# GaN_Fet_ESC_V0_1.net
KiCad netlist of a schematic drawn in EAGLE
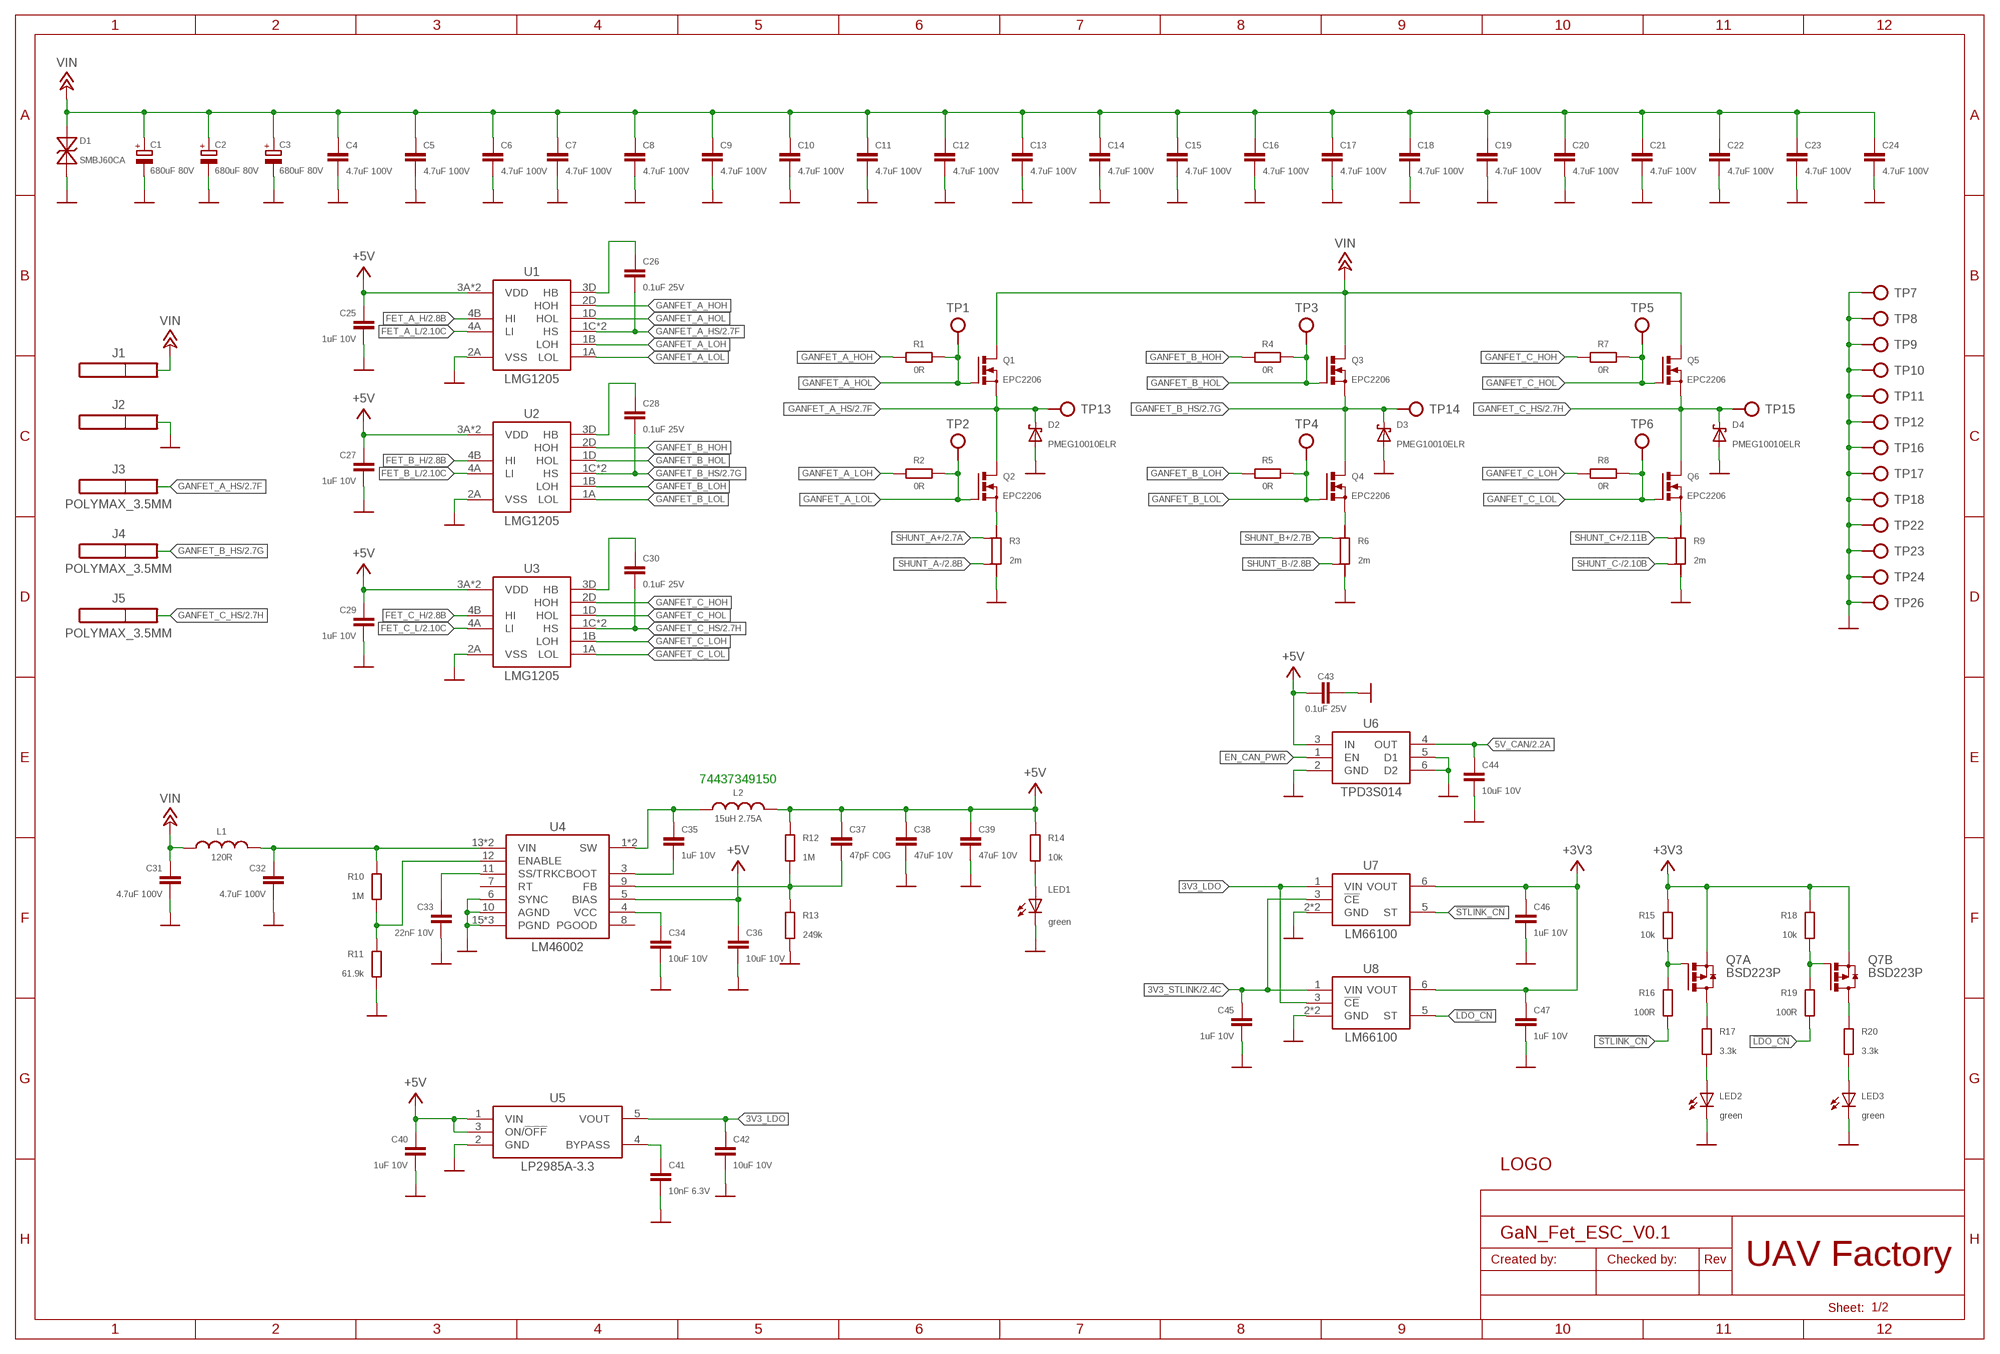
[diagram p0: schematic, sheet 1]
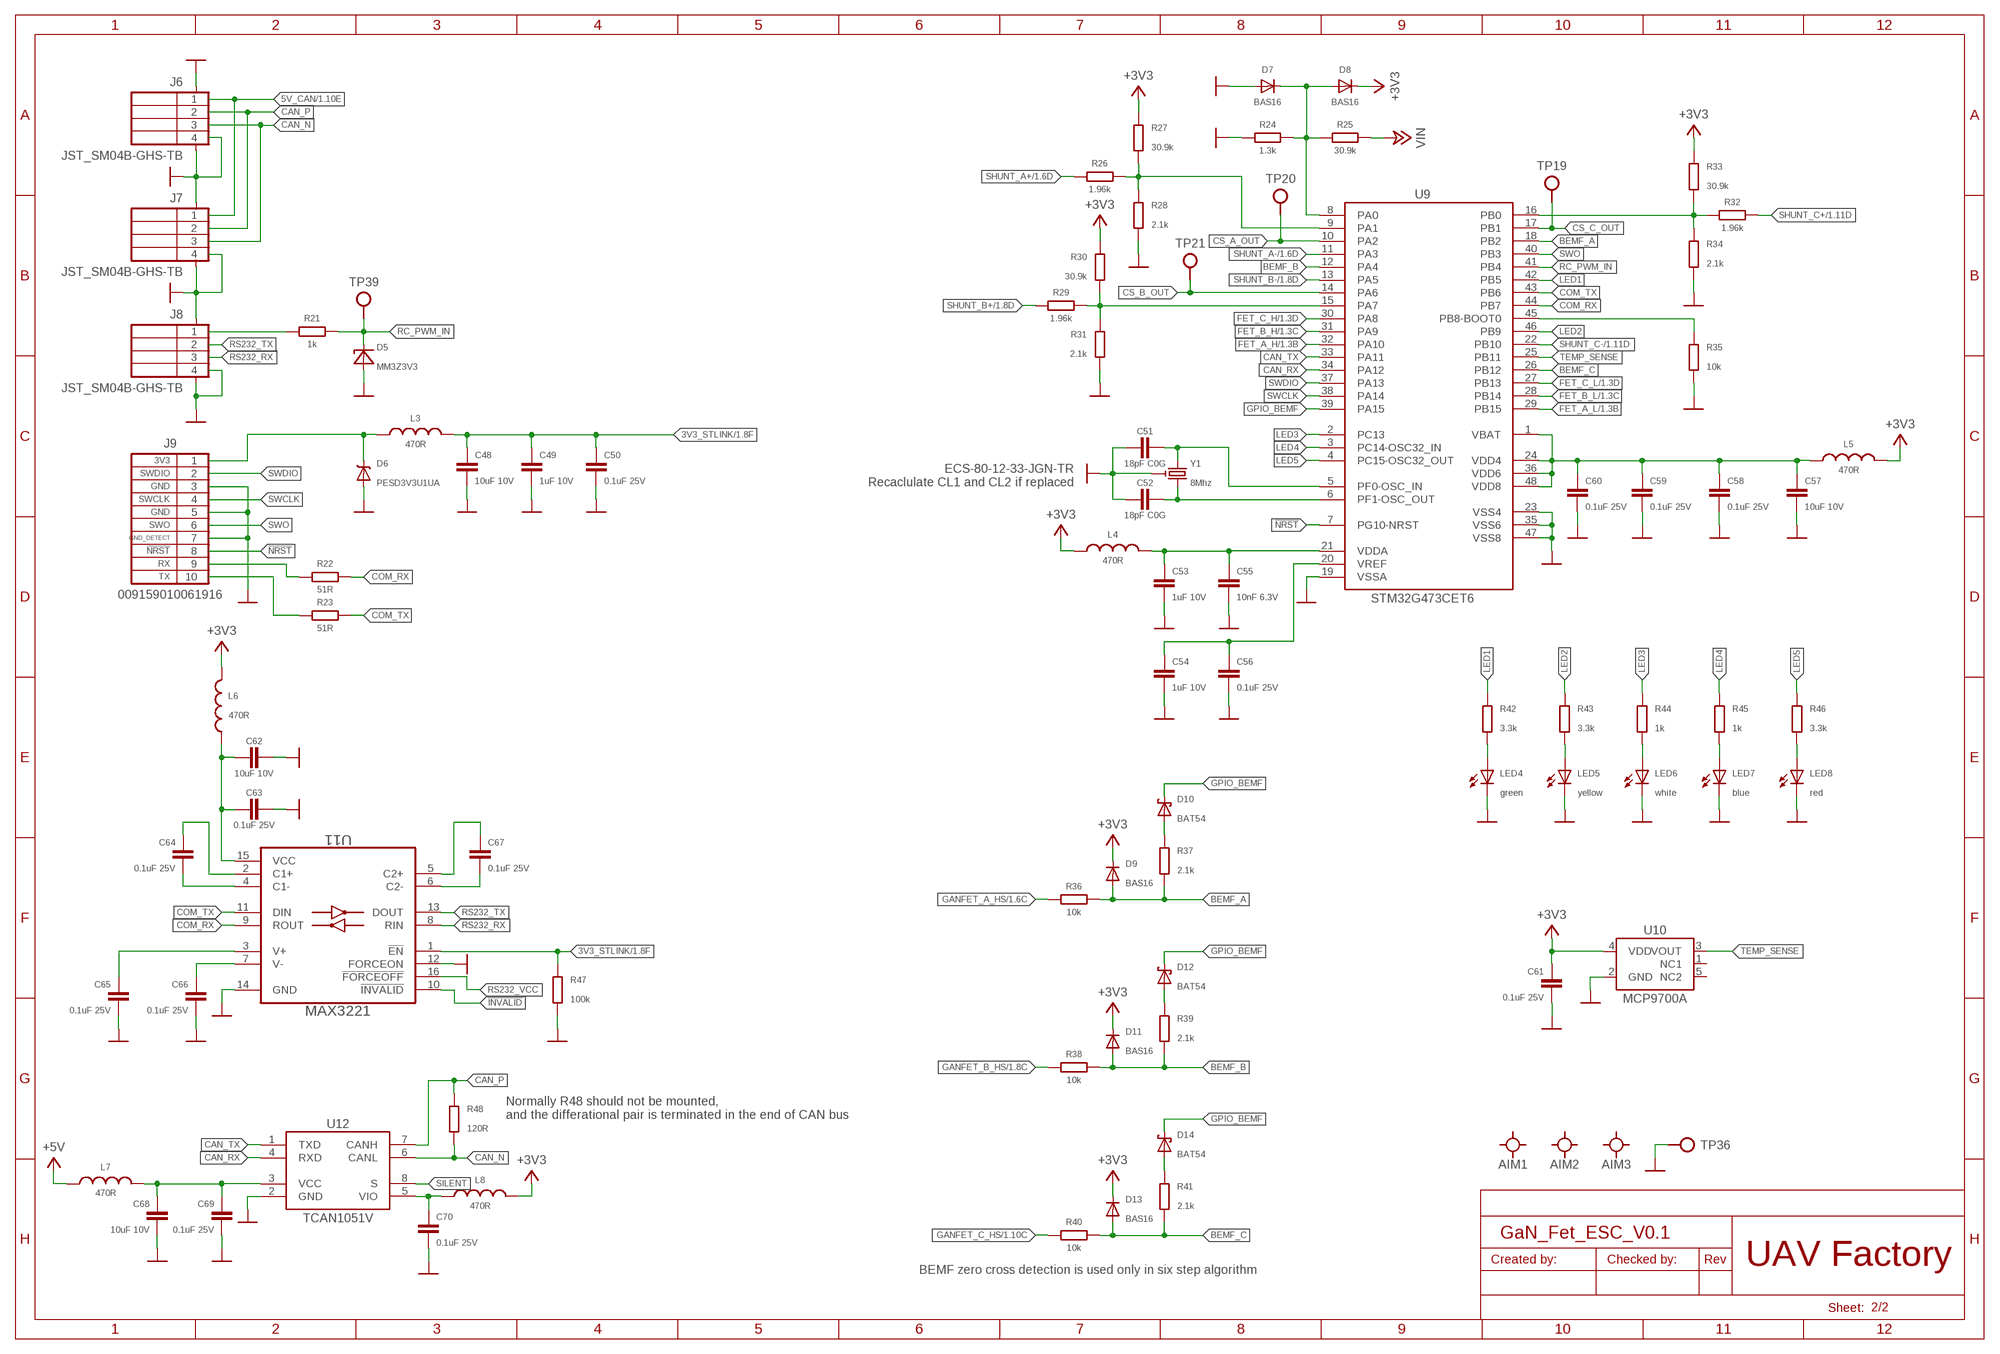
[diagram p1: schematic, sheet 2]

(export (version "E")
  (design (tool "Eeschema 10.0.6"))
  (components
    (comp (ref "AIM1")
      (value "AIM_1_MM")
      (footprint "eagle-import:AIM_1_MM")
      (libsource (lib "eagle-import") (part "AIM_1_MM"))
    )
    (comp (ref "AIM2")
      (value "AIM_1_MM")
      (footprint "eagle-import:AIM_1_MM")
      (libsource (lib "eagle-import") (part "AIM_1_MM"))
    )
    (comp (ref "AIM3")
      (value "AIM_1_MM")
      (footprint "eagle-import:AIM_1_MM")
      (libsource (lib "eagle-import") (part "AIM_1_MM"))
    )
    (comp (ref "C48")
      (value "10uF 10V")
      (footprint "eagle-import:C0603")
      (libsource (lib "eagle-import") (part "CAPACITOR_CERAMIC/0603"))
    )
    (comp (ref "C49")
      (value "1uF 10V")
      (footprint "eagle-import:C0402")
      (libsource (lib "eagle-import") (part "CAPACITOR_CERAMIC/0402"))
    )
    (comp (ref "C50")
      (value "0.1uF 25V")
      (footprint "eagle-import:C0402")
      (libsource (lib "eagle-import") (part "CAPACITOR_CERAMIC/0402"))
    )
    (comp (ref "C51")
      (value "18pF C0G")
      (footprint "eagle-import:C0402")
      (libsource (lib "eagle-import") (part "CAPACITOR_CERAMIC/0402"))
    )
    (comp (ref "C52")
      (value "18pF C0G")
      (footprint "eagle-import:C0402")
      (libsource (lib "eagle-import") (part "CAPACITOR_CERAMIC/0402"))
    )
    (comp (ref "C53")
      (value "1uF 10V")
      (footprint "eagle-import:C0402")
      (libsource (lib "eagle-import") (part "CAPACITOR_CERAMIC/0402"))
    )
    (comp (ref "C54")
      (value "1uF 10V")
      (footprint "eagle-import:C0402")
      (libsource (lib "eagle-import") (part "CAPACITOR_CERAMIC/0402"))
    )
    (comp (ref "C55")
      (value "10nF 6.3V")
      (footprint "eagle-import:C0402")
      (libsource (lib "eagle-import") (part "CAPACITOR_CERAMIC/0402"))
    )
    (comp (ref "C56")
      (value "0.1uF 25V")
      (footprint "eagle-import:C0402")
      (libsource (lib "eagle-import") (part "CAPACITOR_CERAMIC/0402"))
    )
    (comp (ref "C57")
      (value "10uF 10V")
      (footprint "eagle-import:C0603")
      (libsource (lib "eagle-import") (part "CAPACITOR_CERAMIC/0603"))
    )
    (comp (ref "C58")
      (value "0.1uF 25V")
      (footprint "eagle-import:C0402")
      (libsource (lib "eagle-import") (part "CAPACITOR_CERAMIC/0402"))
    )
    (comp (ref "C59")
      (value "0.1uF 25V")
      (footprint "eagle-import:C0402")
      (libsource (lib "eagle-import") (part "CAPACITOR_CERAMIC/0402"))
    )
    (comp (ref "C60")
      (value "0.1uF 25V")
      (footprint "eagle-import:C0402")
      (libsource (lib "eagle-import") (part "CAPACITOR_CERAMIC/0402"))
    )
    (comp (ref "C61")
      (value "0.1uF 25V")
      (footprint "eagle-import:C0402")
      (libsource (lib "eagle-import") (part "CAPACITOR_CERAMIC/0402"))
    )
    (comp (ref "C62")
      (value "10uF 10V")
      (footprint "eagle-import:C0603")
      (libsource (lib "eagle-import") (part "CAPACITOR_CERAMIC/0603"))
    )
    (comp (ref "C63")
      (value "0.1uF 25V")
      (footprint "eagle-import:C0402")
      (libsource (lib "eagle-import") (part "CAPACITOR_CERAMIC/0402"))
    )
    (comp (ref "C64")
      (value "0.1uF 25V")
      (footprint "eagle-import:C0402")
      (libsource (lib "eagle-import") (part "CAPACITOR_CERAMIC/0402"))
    )
    (comp (ref "C65")
      (value "0.1uF 25V")
      (footprint "eagle-import:C0402")
      (libsource (lib "eagle-import") (part "CAPACITOR_CERAMIC/0402"))
    )
    (comp (ref "C66")
      (value "0.1uF 25V")
      (footprint "eagle-import:C0402")
      (libsource (lib "eagle-import") (part "CAPACITOR_CERAMIC/0402"))
    )
    (comp (ref "C67")
      (value "0.1uF 25V")
      (footprint "eagle-import:C0402")
      (libsource (lib "eagle-import") (part "CAPACITOR_CERAMIC/0402"))
    )
    (comp (ref "C68")
      (value "10uF 10V")
      (footprint "eagle-import:C0603")
      (libsource (lib "eagle-import") (part "CAPACITOR_CERAMIC/0603"))
    )
    (comp (ref "C69")
      (value "0.1uF 25V")
      (footprint "eagle-import:C0402")
      (libsource (lib "eagle-import") (part "CAPACITOR_CERAMIC/0402"))
    )
    (comp (ref "C70")
      (value "0.1uF 25V")
      (footprint "eagle-import:C0402")
      (libsource (lib "eagle-import") (part "CAPACITOR_CERAMIC/0402"))
    )
    (comp (ref "D5")
      (value "MM3Z3V3")
      (footprint "eagle-import:SOD323F")
      (libsource (lib "eagle-import") (part "DIODE_ZENER"))
    )
    (comp (ref "D6")
      (value "PESD3V3U1UA")
      (footprint "eagle-import:SOD323F")
      (libsource (lib "eagle-import") (part "DIODE_TVS_UNIDIR/SOD323"))
    )
    (comp (ref "D7")
      (value "BAS16")
      (footprint "eagle-import:SOD523")
      (libsource (lib "eagle-import") (part "DIODE/SOD523"))
    )
    (comp (ref "D8")
      (value "BAS16")
      (footprint "eagle-import:SOD523")
      (libsource (lib "eagle-import") (part "DIODE/SOD523"))
    )
    (comp (ref "D9")
      (value "BAS16")
      (footprint "eagle-import:SOD523")
      (libsource (lib "eagle-import") (part "DIODE/SOD523"))
    )
    (comp (ref "D10")
      (value "BAT54")
      (footprint "eagle-import:SOD523")
      (libsource (lib "eagle-import") (part "DIODE_SCHOTTKY/SOD523"))
    )
    (comp (ref "D11")
      (value "BAS16")
      (footprint "eagle-import:SOD523")
      (libsource (lib "eagle-import") (part "DIODE/SOD523"))
    )
    (comp (ref "D12")
      (value "BAT54")
      (footprint "eagle-import:SOD523")
      (libsource (lib "eagle-import") (part "DIODE_SCHOTTKY/SOD523"))
    )
    (comp (ref "D13")
      (value "BAS16")
      (footprint "eagle-import:SOD523")
      (libsource (lib "eagle-import") (part "DIODE/SOD523"))
    )
    (comp (ref "D14")
      (value "BAT54")
      (footprint "eagle-import:SOD523")
      (libsource (lib "eagle-import") (part "DIODE_SCHOTTKY/SOD523"))
    )
    (comp (ref "J6")
      (value "JST_SM04B-GHS-TB")
      (footprint "eagle-import:JST_SM04B-GHS-TB")
      (libsource (lib "eagle-import") (part "JST_SM04B-GHS-TB"))
    )
    (comp (ref "J7")
      (value "JST_SM04B-GHS-TB")
      (footprint "eagle-import:JST_SM04B-GHS-TB")
      (libsource (lib "eagle-import") (part "JST_SM04B-GHS-TB"))
    )
    (comp (ref "J8")
      (value "JST_SM04B-GHS-TB")
      (footprint "eagle-import:JST_SM04B-GHS-TB")
      (libsource (lib "eagle-import") (part "JST_SM04B-GHS-TB"))
    )
    (comp (ref "J9")
      (value "009159010061916")
      (footprint "eagle-import:009159010061916")
      (libsource (lib "eagle-import") (part "009159010061916"))
    )
    (comp (ref "L3")
      (value "470R")
      (footprint "eagle-import:L0603")
      (libsource (lib "eagle-import") (part "INDUCTOR/0603"))
    )
    (comp (ref "L4")
      (value "470R")
      (footprint "eagle-import:L0603")
      (libsource (lib "eagle-import") (part "INDUCTOR/0603"))
    )
    (comp (ref "L5")
      (value "470R")
      (footprint "eagle-import:L0603")
      (libsource (lib "eagle-import") (part "INDUCTOR/0603"))
    )
    (comp (ref "L6")
      (value "470R")
      (footprint "eagle-import:L0603")
      (libsource (lib "eagle-import") (part "INDUCTOR/0603"))
    )
    (comp (ref "L7")
      (value "470R")
      (footprint "eagle-import:L0603")
      (libsource (lib "eagle-import") (part "INDUCTOR/0603"))
    )
    (comp (ref "L8")
      (value "470R")
      (footprint "eagle-import:L0603")
      (libsource (lib "eagle-import") (part "INDUCTOR/0603"))
    )
    (comp (ref "LED4")
      (value "green")
      (footprint "eagle-import:CHIP-LED0603")
      (libsource (lib "eagle-import") (part "LED/0603"))
    )
    (comp (ref "LED5")
      (value "yellow")
      (footprint "eagle-import:CHIP-LED0603")
      (libsource (lib "eagle-import") (part "LED/0603"))
    )
    (comp (ref "LED6")
      (value "white")
      (footprint "eagle-import:CHIP-LED0603")
      (libsource (lib "eagle-import") (part "LED/0603"))
    )
    (comp (ref "LED7")
      (value "blue")
      (footprint "eagle-import:CHIP-LED0603")
      (libsource (lib "eagle-import") (part "LED/0603"))
    )
    (comp (ref "LED8")
      (value "red")
      (footprint "eagle-import:CHIP-LED0603")
      (libsource (lib "eagle-import") (part "LED/0603"))
    )
    (comp (ref "R21")
      (value "1k")
      (footprint "eagle-import:R0402")
      (libsource (lib "eagle-import") (part "RESISTOR_SMD/0402"))
    )
    (comp (ref "R22")
      (value "51R")
      (footprint "eagle-import:R0402")
      (libsource (lib "eagle-import") (part "RESISTOR_SMD/0402"))
    )
    (comp (ref "R23")
      (value "51R")
      (footprint "eagle-import:R0402")
      (libsource (lib "eagle-import") (part "RESISTOR_SMD/0402"))
    )
    (comp (ref "R24")
      (value "1.3k")
      (footprint "eagle-import:R0603")
      (libsource (lib "eagle-import") (part "RESISTOR_SMD/0603"))
    )
    (comp (ref "R25")
      (value "30.9k")
      (footprint "eagle-import:R0603")
      (libsource (lib "eagle-import") (part "RESISTOR_SMD/0603"))
    )
    (comp (ref "R26")
      (value "1.96k")
      (footprint "eagle-import:R0402")
      (libsource (lib "eagle-import") (part "RESISTOR_SMD/0402"))
    )
    (comp (ref "R27")
      (value "30.9k")
      (footprint "eagle-import:R0402")
      (libsource (lib "eagle-import") (part "RESISTOR_SMD/0402"))
    )
    (comp (ref "R28")
      (value "2.1k")
      (footprint "eagle-import:R0402")
      (libsource (lib "eagle-import") (part "RESISTOR_SMD/0402"))
    )
    (comp (ref "R29")
      (value "1.96k")
      (footprint "eagle-import:R0402")
      (libsource (lib "eagle-import") (part "RESISTOR_SMD/0402"))
    )
    (comp (ref "R30")
      (value "30.9k")
      (footprint "eagle-import:R0402")
      (libsource (lib "eagle-import") (part "RESISTOR_SMD/0402"))
    )
    (comp (ref "R31")
      (value "2.1k")
      (footprint "eagle-import:R0402")
      (libsource (lib "eagle-import") (part "RESISTOR_SMD/0402"))
    )
    (comp (ref "R32")
      (value "1.96k")
      (footprint "eagle-import:R0402")
      (libsource (lib "eagle-import") (part "RESISTOR_SMD/0402"))
    )
    (comp (ref "R33")
      (value "30.9k")
      (footprint "eagle-import:R0402")
      (libsource (lib "eagle-import") (part "RESISTOR_SMD/0402"))
    )
    (comp (ref "R34")
      (value "2.1k")
      (footprint "eagle-import:R0402")
      (libsource (lib "eagle-import") (part "RESISTOR_SMD/0402"))
    )
    (comp (ref "R35")
      (value "10k")
      (footprint "eagle-import:R0402")
      (libsource (lib "eagle-import") (part "RESISTOR_SMD/0402"))
    )
    (comp (ref "R36")
      (value "10k")
      (footprint "eagle-import:R0402")
      (libsource (lib "eagle-import") (part "RESISTOR_SMD/0402"))
    )
    (comp (ref "R37")
      (value "2.1k")
      (footprint "eagle-import:R0402")
      (libsource (lib "eagle-import") (part "RESISTOR_SMD/0402"))
    )
    (comp (ref "R38")
      (value "10k")
      (footprint "eagle-import:R0402")
      (libsource (lib "eagle-import") (part "RESISTOR_SMD/0402"))
    )
    (comp (ref "R39")
      (value "2.1k")
      (footprint "eagle-import:R0402")
      (libsource (lib "eagle-import") (part "RESISTOR_SMD/0402"))
    )
    (comp (ref "R40")
      (value "10k")
      (footprint "eagle-import:R0402")
      (libsource (lib "eagle-import") (part "RESISTOR_SMD/0402"))
    )
    (comp (ref "R41")
      (value "2.1k")
      (footprint "eagle-import:R0402")
      (libsource (lib "eagle-import") (part "RESISTOR_SMD/0402"))
    )
    (comp (ref "R42")
      (value "3.3k")
      (footprint "eagle-import:R0402")
      (libsource (lib "eagle-import") (part "RESISTOR_SMD/0402"))
    )
    (comp (ref "R43")
      (value "3.3k")
      (footprint "eagle-import:R0402")
      (libsource (lib "eagle-import") (part "RESISTOR_SMD/0402"))
    )
    (comp (ref "R44")
      (value "1k")
      (footprint "eagle-import:R0402")
      (libsource (lib "eagle-import") (part "RESISTOR_SMD/0402"))
    )
    (comp (ref "R45")
      (value "1k")
      (footprint "eagle-import:R0402")
      (libsource (lib "eagle-import") (part "RESISTOR_SMD/0402"))
    )
    (comp (ref "R46")
      (value "3.3k")
      (footprint "eagle-import:R0402")
      (libsource (lib "eagle-import") (part "RESISTOR_SMD/0402"))
    )
    (comp (ref "R47")
      (value "100k")
      (footprint "eagle-import:R0402")
      (libsource (lib "eagle-import") (part "RESISTOR_SMD/0402"))
    )
    (comp (ref "R48")
      (value "120R")
      (footprint "eagle-import:R0805")
      (libsource (lib "eagle-import") (part "RESISTOR_SMD/0805"))
    )
    (comp (ref "TP19")
      (value "TESTPOINT/0.9MM")
      (footprint "eagle-import:0.9MM")
      (libsource (lib "eagle-import") (part "TESTPOINT/0.9MM"))
    )
    (comp (ref "TP20")
      (value "TESTPOINT/0.9MM")
      (footprint "eagle-import:0.9MM")
      (libsource (lib "eagle-import") (part "TESTPOINT/0.9MM"))
    )
    (comp (ref "TP21")
      (value "TESTPOINT/0.9MM")
      (footprint "eagle-import:0.9MM")
      (libsource (lib "eagle-import") (part "TESTPOINT/0.9MM"))
    )
    (comp (ref "TP36")
      (value "TESTPOINT0.5MM")
      (footprint "eagle-import:0.5MM")
      (libsource (lib "eagle-import") (part "TESTPOINT0.5MM"))
    )
    (comp (ref "TP39")
      (value "TESTPOINT/0.9MM")
      (footprint "eagle-import:0.9MM")
      (libsource (lib "eagle-import") (part "TESTPOINT/0.9MM"))
    )
    (comp (ref "U9")
      (value "STM32G473CET6")
      (footprint "eagle-import:LQFP-48")
      (libsource (lib "eagle-import") (part "STM32G4_48"))
    )
    (comp (ref "U10")
      (value "MCP9700A")
      (footprint "eagle-import:SC-70-5")
      (libsource (lib "eagle-import") (part "MCP9700"))
    )
    (comp (ref "U11")
      (value "MAX3221")
      (footprint "eagle-import:TSS0P16")
      (libsource (lib "eagle-import") (part "MAX3221"))
    )
    (comp (ref "U12")
      (value "TCAN1051V")
      (footprint "eagle-import:SOIC-8")
      (libsource (lib "eagle-import") (part "TCAN1051V"))
    )
    (comp (ref "Y1")
      (value "8Mhz")
      (footprint "eagle-import:CRYSTAL_SMD_3.2X2.5MM")
      (libsource (lib "eagle-import") (part "CRYSTAL_GROUNDED/SMD_3.2X2.5MM"))
    )
    (comp (ref "C1")
      (value "680uF 80V")
      (footprint "eagle-import:C_7.50_16_26.5_1")
      (libsource (lib "eagle-import") (part "CAPACITOR_ELECTROLYTIC1"))
    )
    (comp (ref "C2")
      (value "680uF 80V")
      (footprint "eagle-import:C_7.50_16_26.5_2")
      (libsource (lib "eagle-import") (part "CAPACITOR_ELECTROLYTIC2"))
    )
    (comp (ref "C3")
      (value "680uF 80V")
      (footprint "eagle-import:C_7.50_16_26.5_3")
      (libsource (lib "eagle-import") (part "CAPACITOR_ELECTROLYTIC3"))
    )
    (comp (ref "C4")
      (value "4.7uF 100V")
      (footprint "eagle-import:C1210")
      (libsource (lib "eagle-import") (part "CAPACITOR_CERAMIC/1210"))
    )
    (comp (ref "C5")
      (value "4.7uF 100V")
      (footprint "eagle-import:C1210")
      (libsource (lib "eagle-import") (part "CAPACITOR_CERAMIC/1210"))
    )
    (comp (ref "C6")
      (value "4.7uF 100V")
      (footprint "eagle-import:C1210")
      (libsource (lib "eagle-import") (part "CAPACITOR_CERAMIC/1210"))
    )
    (comp (ref "C7")
      (value "4.7uF 100V")
      (footprint "eagle-import:C1210")
      (libsource (lib "eagle-import") (part "CAPACITOR_CERAMIC/1210"))
    )
    (comp (ref "C8")
      (value "4.7uF 100V")
      (footprint "eagle-import:C1210")
      (libsource (lib "eagle-import") (part "CAPACITOR_CERAMIC/1210"))
    )
    (comp (ref "C9")
      (value "4.7uF 100V")
      (footprint "eagle-import:C1210")
      (libsource (lib "eagle-import") (part "CAPACITOR_CERAMIC/1210"))
    )
    (comp (ref "C10")
      (value "4.7uF 100V")
      (footprint "eagle-import:C1210")
      (libsource (lib "eagle-import") (part "CAPACITOR_CERAMIC/1210"))
    )
    (comp (ref "C11")
      (value "4.7uF 100V")
      (footprint "eagle-import:C1210")
      (libsource (lib "eagle-import") (part "CAPACITOR_CERAMIC/1210"))
    )
    (comp (ref "C12")
      (value "4.7uF 100V")
      (footprint "eagle-import:C1210")
      (libsource (lib "eagle-import") (part "CAPACITOR_CERAMIC/1210"))
    )
    (comp (ref "C13")
      (value "4.7uF 100V")
      (footprint "eagle-import:C1210")
      (libsource (lib "eagle-import") (part "CAPACITOR_CERAMIC/1210"))
    )
    (comp (ref "C14")
      (value "4.7uF 100V")
      (footprint "eagle-import:C1210")
      (libsource (lib "eagle-import") (part "CAPACITOR_CERAMIC/1210"))
    )
    (comp (ref "C15")
      (value "4.7uF 100V")
      (footprint "eagle-import:C1210")
      (libsource (lib "eagle-import") (part "CAPACITOR_CERAMIC/1210"))
    )
    (comp (ref "C16")
      (value "4.7uF 100V")
      (footprint "eagle-import:C1210")
      (libsource (lib "eagle-import") (part "CAPACITOR_CERAMIC/1210"))
    )
    (comp (ref "C17")
      (value "4.7uF 100V")
      (footprint "eagle-import:C1210")
      (libsource (lib "eagle-import") (part "CAPACITOR_CERAMIC/1210"))
    )
    (comp (ref "C18")
      (value "4.7uF 100V")
      (footprint "eagle-import:C1210")
      (libsource (lib "eagle-import") (part "CAPACITOR_CERAMIC/1210"))
    )
    (comp (ref "C19")
      (value "4.7uF 100V")
      (footprint "eagle-import:C1210")
      (libsource (lib "eagle-import") (part "CAPACITOR_CERAMIC/1210"))
    )
    (comp (ref "C20")
      (value "4.7uF 100V")
      (footprint "eagle-import:C1210")
      (libsource (lib "eagle-import") (part "CAPACITOR_CERAMIC/1210"))
    )
    (comp (ref "C21")
      (value "4.7uF 100V")
      (footprint "eagle-import:C1210")
      (libsource (lib "eagle-import") (part "CAPACITOR_CERAMIC/1210"))
    )
    (comp (ref "C22")
      (value "4.7uF 100V")
      (footprint "eagle-import:C1210")
      (libsource (lib "eagle-import") (part "CAPACITOR_CERAMIC/1210"))
    )
    (comp (ref "C23")
      (value "4.7uF 100V")
      (footprint "eagle-import:C1210")
      (libsource (lib "eagle-import") (part "CAPACITOR_CERAMIC/1210"))
    )
    (comp (ref "C24")
      (value "4.7uF 100V")
      (footprint "eagle-import:C1210")
      (libsource (lib "eagle-import") (part "CAPACITOR_CERAMIC/1210"))
    )
    (comp (ref "C25")
      (value "1uF 10V")
      (footprint "eagle-import:C0402")
      (libsource (lib "eagle-import") (part "CAPACITOR_CERAMIC/0402"))
    )
    (comp (ref "C26")
      (value "0.1uF 25V")
      (footprint "eagle-import:C0402")
      (libsource (lib "eagle-import") (part "CAPACITOR_CERAMIC/0402"))
    )
    (comp (ref "C27")
      (value "1uF 10V")
      (footprint "eagle-import:C0402")
      (libsource (lib "eagle-import") (part "CAPACITOR_CERAMIC/0402"))
    )
    (comp (ref "C28")
      (value "0.1uF 25V")
      (footprint "eagle-import:C0402")
      (libsource (lib "eagle-import") (part "CAPACITOR_CERAMIC/0402"))
    )
    (comp (ref "C29")
      (value "1uF 10V")
      (footprint "eagle-import:C0402")
      (libsource (lib "eagle-import") (part "CAPACITOR_CERAMIC/0402"))
    )
    (comp (ref "C30")
      (value "0.1uF 25V")
      (footprint "eagle-import:C0402")
      (libsource (lib "eagle-import") (part "CAPACITOR_CERAMIC/0402"))
    )
    (comp (ref "C31")
      (value "4.7uF 100V")
      (footprint "eagle-import:C1210")
      (libsource (lib "eagle-import") (part "CAPACITOR_CERAMIC/1210"))
    )
    (comp (ref "C32")
      (value "4.7uF 100V")
      (footprint "eagle-import:C1210")
      (libsource (lib "eagle-import") (part "CAPACITOR_CERAMIC/1210"))
    )
    (comp (ref "C33")
      (value "22nF 10V")
      (footprint "eagle-import:C0402")
      (libsource (lib "eagle-import") (part "CAPACITOR_CERAMIC/0402"))
    )
    (comp (ref "C34")
      (value "10uF 10V")
      (footprint "eagle-import:C0603")
      (libsource (lib "eagle-import") (part "CAPACITOR_CERAMIC/0603"))
    )
    (comp (ref "C35")
      (value "1uF 10V")
      (footprint "eagle-import:C0402")
      (libsource (lib "eagle-import") (part "CAPACITOR_CERAMIC/0402"))
    )
    (comp (ref "C36")
      (value "10uF 10V")
      (footprint "eagle-import:C0603")
      (libsource (lib "eagle-import") (part "CAPACITOR_CERAMIC/0603"))
    )
    (comp (ref "C37")
      (value "47pF C0G")
      (footprint "eagle-import:C0402")
      (libsource (lib "eagle-import") (part "CAPACITOR_CERAMIC/0402"))
    )
    (comp (ref "C38")
      (value "47uF 10V")
      (footprint "eagle-import:C1206")
      (libsource (lib "eagle-import") (part "CAPACITOR_CERAMIC/1206"))
    )
    (comp (ref "C39")
      (value "47uF 10V")
      (footprint "eagle-import:C1206")
      (libsource (lib "eagle-import") (part "CAPACITOR_CERAMIC/1206"))
    )
    (comp (ref "C40")
      (value "1uF 10V")
      (footprint "eagle-import:C0402")
      (libsource (lib "eagle-import") (part "CAPACITOR_CERAMIC/0402"))
    )
    (comp (ref "C41")
      (value "10nF 6.3V")
      (footprint "eagle-import:C0402")
      (libsource (lib "eagle-import") (part "CAPACITOR_CERAMIC/0402"))
    )
    (comp (ref "C42")
      (value "10uF 10V")
      (footprint "eagle-import:C0603")
      (libsource (lib "eagle-import") (part "CAPACITOR_CERAMIC/0603"))
    )
    (comp (ref "C43")
      (value "0.1uF 25V")
      (footprint "eagle-import:C0402")
      (libsource (lib "eagle-import") (part "CAPACITOR_CERAMIC/0402"))
    )
    (comp (ref "C44")
      (value "10uF 10V")
      (footprint "eagle-import:C0603")
      (libsource (lib "eagle-import") (part "CAPACITOR_CERAMIC/0603"))
    )
    (comp (ref "C45")
      (value "1uF 10V")
      (footprint "eagle-import:C0402")
      (libsource (lib "eagle-import") (part "CAPACITOR_CERAMIC/0402"))
    )
    (comp (ref "C46")
      (value "1uF 10V")
      (footprint "eagle-import:C0402")
      (libsource (lib "eagle-import") (part "CAPACITOR_CERAMIC/0402"))
    )
    (comp (ref "C47")
      (value "1uF 10V")
      (footprint "eagle-import:C0402")
      (libsource (lib "eagle-import") (part "CAPACITOR_CERAMIC/0402"))
    )
    (comp (ref "D1")
      (value "SMBJ60CA")
      (footprint "eagle-import:DO214AA(SMB)")
      (libsource (lib "eagle-import") (part "DIODE_TVS_BIDIR/SMB"))
    )
    (comp (ref "D2")
      (value "PMEG10010ELR")
      (footprint "eagle-import:SOD123F")
      (libsource (lib "eagle-import") (part "DIODE_SCHOTTKY/SOD123"))
    )
    (comp (ref "D3")
      (value "PMEG10010ELR")
      (footprint "eagle-import:SOD123F")
      (libsource (lib "eagle-import") (part "DIODE_SCHOTTKY/SOD123"))
    )
    (comp (ref "D4")
      (value "PMEG10010ELR")
      (footprint "eagle-import:SOD123F")
      (libsource (lib "eagle-import") (part "DIODE_SCHOTTKY/SOD123"))
    )
    (comp (ref "J1")
      (value "PIN_14X10")
      (footprint "eagle-import:4X10SMD")
      (libsource (lib "eagle-import") (part "PIN_14X10"))
    )
    (comp (ref "J2")
      (value "PIN_14X10")
      (footprint "eagle-import:4X10SMD")
      (libsource (lib "eagle-import") (part "PIN_14X10"))
    )
    (comp (ref "J3")
      (value "POLYMAX_3.5MM")
      (footprint "eagle-import:POLYMAX_3.5MM")
      (libsource (lib "eagle-import") (part "POLYMAX_3.5MM"))
    )
    (comp (ref "J4")
      (value "POLYMAX_3.5MM")
      (footprint "eagle-import:POLYMAX_3.5MM")
      (libsource (lib "eagle-import") (part "POLYMAX_3.5MM"))
    )
    (comp (ref "J5")
      (value "POLYMAX_3.5MM")
      (footprint "eagle-import:POLYMAX_3.5MM")
      (libsource (lib "eagle-import") (part "POLYMAX_3.5MM"))
    )
    (comp (ref "L1")
      (value "120R")
      (footprint "eagle-import:L1206")
      (libsource (lib "eagle-import") (part "INDUCTOR/1206"))
    )
    (comp (ref "L2")
      (value "15uH 2.75A")
      (footprint "eagle-import:WURTH_6.6X6.6")
      (libsource (lib "eagle-import") (part "INDUCTOR/WE-LHMI"))
    )
    (comp (ref "LED1")
      (value "green")
      (footprint "eagle-import:CHIP-LED0603")
      (libsource (lib "eagle-import") (part "LED/0603"))
    )
    (comp (ref "LED2")
      (value "green")
      (footprint "eagle-import:CHIP-LED0603")
      (libsource (lib "eagle-import") (part "LED/0603"))
    )
    (comp (ref "LED3")
      (value "green")
      (footprint "eagle-import:CHIP-LED0603")
      (libsource (lib "eagle-import") (part "LED/0603"))
    )
    (comp (ref "Q1")
      (value "EPC2206")
      (footprint "eagle-import:EPC2206")
      (libsource (lib "eagle-import") (part "GAN-N-FET"))
    )
    (comp (ref "Q2")
      (value "EPC2206")
      (footprint "eagle-import:EPC2206")
      (libsource (lib "eagle-import") (part "GAN-N-FET"))
    )
    (comp (ref "Q3")
      (value "EPC2206")
      (footprint "eagle-import:EPC2206")
      (libsource (lib "eagle-import") (part "GAN-N-FET"))
    )
    (comp (ref "Q4")
      (value "EPC2206")
      (footprint "eagle-import:EPC2206")
      (libsource (lib "eagle-import") (part "GAN-N-FET"))
    )
    (comp (ref "Q5")
      (value "EPC2206")
      (footprint "eagle-import:EPC2206")
      (libsource (lib "eagle-import") (part "GAN-N-FET"))
    )
    (comp (ref "Q6")
      (value "EPC2206")
      (footprint "eagle-import:EPC2206")
      (libsource (lib "eagle-import") (part "GAN-N-FET"))
    )
    (comp (ref "Q7")
      (value "BSD223P")
      (footprint "eagle-import:SC-70-6")
      (libsource (lib "eagle-import") (part "P-FET"))
    )
    (comp (ref "R1")
      (value "0R")
      (footprint "eagle-import:R0402")
      (libsource (lib "eagle-import") (part "RESISTOR_SMD/0402"))
    )
    (comp (ref "R2")
      (value "0R")
      (footprint "eagle-import:R0402")
      (libsource (lib "eagle-import") (part "RESISTOR_SMD/0402"))
    )
    (comp (ref "R3")
      (value "2m")
      (footprint "eagle-import:CSS2H-2512")
      (libsource (lib "eagle-import") (part "RESISTOR_KELVIN/CRF2512"))
    )
    (comp (ref "R4")
      (value "0R")
      (footprint "eagle-import:R0402")
      (libsource (lib "eagle-import") (part "RESISTOR_SMD/0402"))
    )
    (comp (ref "R5")
      (value "0R")
      (footprint "eagle-import:R0402")
      (libsource (lib "eagle-import") (part "RESISTOR_SMD/0402"))
    )
    (comp (ref "R6")
      (value "2m")
      (footprint "eagle-import:CSS2H-2512")
      (libsource (lib "eagle-import") (part "RESISTOR_KELVIN/CRF2512"))
    )
    (comp (ref "R7")
      (value "0R")
      (footprint "eagle-import:R0402")
      (libsource (lib "eagle-import") (part "RESISTOR_SMD/0402"))
    )
    (comp (ref "R8")
      (value "0R")
      (footprint "eagle-import:R0402")
      (libsource (lib "eagle-import") (part "RESISTOR_SMD/0402"))
    )
    (comp (ref "R9")
      (value "2m")
      (footprint "eagle-import:CSS2H-2512")
      (libsource (lib "eagle-import") (part "RESISTOR_KELVIN/CRF2512"))
    )
    (comp (ref "R10")
      (value "1M")
      (footprint "eagle-import:R0603")
      (libsource (lib "eagle-import") (part "RESISTOR_SMD/0603"))
    )
    (comp (ref "R11")
      (value "61.9k")
      (footprint "eagle-import:R0603")
      (libsource (lib "eagle-import") (part "RESISTOR_SMD/0603"))
    )
    (comp (ref "R12")
      (value "1M")
      (footprint "eagle-import:R0402")
      (libsource (lib "eagle-import") (part "RESISTOR_SMD/0402"))
    )
    (comp (ref "R13")
      (value "249k")
      (footprint "eagle-import:R0402")
      (libsource (lib "eagle-import") (part "RESISTOR_SMD/0402"))
    )
    (comp (ref "R14")
      (value "10k")
      (footprint "eagle-import:R0402")
      (libsource (lib "eagle-import") (part "RESISTOR_SMD/0402"))
    )
    (comp (ref "R15")
      (value "10k")
      (footprint "eagle-import:R0402")
      (libsource (lib "eagle-import") (part "RESISTOR_SMD/0402"))
    )
    (comp (ref "R16")
      (value "100R")
      (footprint "eagle-import:R0402")
      (libsource (lib "eagle-import") (part "RESISTOR_SMD/0402"))
    )
    (comp (ref "R17")
      (value "3.3k")
      (footprint "eagle-import:R0402")
      (libsource (lib "eagle-import") (part "RESISTOR_SMD/0402"))
    )
    (comp (ref "R18")
      (value "10k")
      (footprint "eagle-import:R0402")
      (libsource (lib "eagle-import") (part "RESISTOR_SMD/0402"))
    )
    (comp (ref "R19")
      (value "100R")
      (footprint "eagle-import:R0402")
      (libsource (lib "eagle-import") (part "RESISTOR_SMD/0402"))
    )
    (comp (ref "R20")
      (value "3.3k")
      (footprint "eagle-import:R0402")
      (libsource (lib "eagle-import") (part "RESISTOR_SMD/0402"))
    )
    (comp (ref "TP1")
      (value "TESTPOINT/0.9MM")
      (footprint "eagle-import:0.9MM")
      (libsource (lib "eagle-import") (part "TESTPOINT/0.9MM"))
    )
    (comp (ref "TP2")
      (value "TESTPOINT/0.9MM")
      (footprint "eagle-import:0.9MM")
      (libsource (lib "eagle-import") (part "TESTPOINT/0.9MM"))
    )
    (comp (ref "TP3")
      (value "TESTPOINT/0.9MM")
      (footprint "eagle-import:0.9MM")
      (libsource (lib "eagle-import") (part "TESTPOINT/0.9MM"))
    )
    (comp (ref "TP4")
      (value "TESTPOINT/0.9MM")
      (footprint "eagle-import:0.9MM")
      (libsource (lib "eagle-import") (part "TESTPOINT/0.9MM"))
    )
    (comp (ref "TP5")
      (value "TESTPOINT/0.9MM")
      (footprint "eagle-import:0.9MM")
      (libsource (lib "eagle-import") (part "TESTPOINT/0.9MM"))
    )
    (comp (ref "TP6")
      (value "TESTPOINT/0.9MM")
      (footprint "eagle-import:0.9MM")
      (libsource (lib "eagle-import") (part "TESTPOINT/0.9MM"))
    )
    (comp (ref "TP7")
      (value "TESTPOINT0.5MM")
      (footprint "eagle-import:0.5MM")
      (libsource (lib "eagle-import") (part "TESTPOINT0.5MM"))
    )
    (comp (ref "TP8")
      (value "TESTPOINT0.5MM")
      (footprint "eagle-import:0.5MM")
      (libsource (lib "eagle-import") (part "TESTPOINT0.5MM"))
    )
    (comp (ref "TP9")
      (value "TESTPOINT0.5MM")
      (footprint "eagle-import:0.5MM")
      (libsource (lib "eagle-import") (part "TESTPOINT0.5MM"))
    )
    (comp (ref "TP10")
      (value "TESTPOINT0.5MM")
      (footprint "eagle-import:0.5MM")
      (libsource (lib "eagle-import") (part "TESTPOINT0.5MM"))
    )
    (comp (ref "TP11")
      (value "TESTPOINT0.5MM")
      (footprint "eagle-import:0.5MM")
      (libsource (lib "eagle-import") (part "TESTPOINT0.5MM"))
    )
    (comp (ref "TP12")
      (value "TESTPOINT0.5MM")
      (footprint "eagle-import:0.5MM")
      (libsource (lib "eagle-import") (part "TESTPOINT0.5MM"))
    )
    (comp (ref "TP13")
      (value "TESTPOINT/0.9MM")
      (footprint "eagle-import:0.9MM")
      (libsource (lib "eagle-import") (part "TESTPOINT/0.9MM"))
    )
    (comp (ref "TP14")
      (value "TESTPOINT/0.9MM")
      (footprint "eagle-import:0.9MM")
      (libsource (lib "eagle-import") (part "TESTPOINT/0.9MM"))
    )
    (comp (ref "TP15")
      (value "TESTPOINT/0.9MM")
      (footprint "eagle-import:0.9MM")
      (libsource (lib "eagle-import") (part "TESTPOINT/0.9MM"))
    )
    (comp (ref "TP16")
      (value "TESTPOINT0.5MM")
      (footprint "eagle-import:0.5MM")
      (libsource (lib "eagle-import") (part "TESTPOINT0.5MM"))
    )
    (comp (ref "TP17")
      (value "TESTPOINT0.5MM")
      (footprint "eagle-import:0.5MM")
      (libsource (lib "eagle-import") (part "TESTPOINT0.5MM"))
    )
    (comp (ref "TP18")
      (value "TESTPOINT0.5MM")
      (footprint "eagle-import:0.5MM")
      (libsource (lib "eagle-import") (part "TESTPOINT0.5MM"))
    )
    (comp (ref "TP22")
      (value "TESTPOINT0.5MM")
      (footprint "eagle-import:0.5MM")
      (libsource (lib "eagle-import") (part "TESTPOINT0.5MM"))
    )
    (comp (ref "TP23")
      (value "TESTPOINT0.5MM")
      (footprint "eagle-import:0.5MM")
      (libsource (lib "eagle-import") (part "TESTPOINT0.5MM"))
    )
    (comp (ref "TP24")
      (value "TESTPOINT0.5MM")
      (footprint "eagle-import:0.5MM")
      (libsource (lib "eagle-import") (part "TESTPOINT0.5MM"))
    )
    (comp (ref "TP26")
      (value "TESTPOINT0.5MM")
      (footprint "eagle-import:0.5MM")
      (libsource (lib "eagle-import") (part "TESTPOINT0.5MM"))
    )
    (comp (ref "U$1")
      (value "LOGO")
      (footprint "eagle-import:LOGO")
      (libsource (lib "eagle-import") (part "LOGO"))
    )
    (comp (ref "U1")
      (value "LMG1205")
      (footprint "eagle-import:LMG1205")
      (libsource (lib "eagle-import") (part "LMG1205"))
    )
    (comp (ref "U2")
      (value "LMG1205")
      (footprint "eagle-import:LMG1205")
      (libsource (lib "eagle-import") (part "LMG1205"))
    )
    (comp (ref "U3")
      (value "LMG1205")
      (footprint "eagle-import:LMG1205")
      (libsource (lib "eagle-import") (part "LMG1205"))
    )
    (comp (ref "U4")
      (value "LM46002")
      (footprint "eagle-import:TSS0P16-PAD")
      (libsource (lib "eagle-import") (part "LM46002"))
    )
    (comp (ref "U5")
      (value "LP2985A-3.3")
      (footprint "eagle-import:SOT-23-5")
      (libsource (lib "eagle-import") (part "LP2985"))
    )
    (comp (ref "U6")
      (value "TPD3S014")
      (footprint "eagle-import:SOT-23-6")
      (libsource (lib "eagle-import") (part "TPD3S014"))
    )
    (comp (ref "U7")
      (value "LM66100")
      (footprint "eagle-import:SC-70-6")
      (libsource (lib "eagle-import") (part "LM66100"))
    )
    (comp (ref "U8")
      (value "LM66100")
      (footprint "eagle-import:SC-70-6")
      (libsource (lib "eagle-import") (part "LM66100"))
    )
  )
  (nets
    (net (code "1") (name "+3V3") (class "Default")
      (node (ref "C46") (pin "1") (pinfunction "1_1") (pintype "passive"))
      (node (ref "C47") (pin "1") (pinfunction "1_1") (pintype "passive"))
      (node (ref "C61") (pin "1") (pinfunction "1_1") (pintype "passive"))
      (node (ref "D11") (pin "C") (pinfunction "C_C") (pintype "passive"))
      (node (ref "D13") (pin "C") (pinfunction "C_C") (pintype "passive"))
      (node (ref "D8") (pin "C") (pinfunction "C_C") (pintype "passive"))
      (node (ref "D9") (pin "C") (pinfunction "C_C") (pintype "passive"))
      (node (ref "L4") (pin "1") (pinfunction "1_1") (pintype "passive"))
      (node (ref "L5") (pin "2") (pinfunction "2_2") (pintype "passive"))
      (node (ref "L6") (pin "1") (pinfunction "1_1") (pintype "passive"))
      (node (ref "L8") (pin "2") (pinfunction "2_2") (pintype "passive"))
      (node (ref "Q7") (pin "1") (pinfunction "S_1") (pintype "passive"))
      (node (ref "Q7") (pin "4") (pinfunction "S_4") (pintype "passive"))
      (node (ref "R15") (pin "2") (pinfunction "2_2") (pintype "bidirectional"))
      (node (ref "R18") (pin "2") (pinfunction "2_2") (pintype "bidirectional"))
      (node (ref "R27") (pin "2") (pinfunction "2_2") (pintype "bidirectional"))
      (node (ref "R30") (pin "2") (pinfunction "2_2") (pintype "bidirectional"))
      (node (ref "R33") (pin "2") (pinfunction "2_2") (pintype "bidirectional"))
      (node (ref "U10") (pin "4") (pinfunction "VDD_4") (pintype "bidirectional"))
      (node (ref "U7") (pin "6") (pinfunction "VOUT_6") (pintype "bidirectional"))
      (node (ref "U8") (pin "6") (pinfunction "VOUT_6") (pintype "bidirectional"))
    )
    (net (code "2") (name "+5V") (class "Default")
      (node (ref "C25") (pin "1") (pinfunction "1_1") (pintype "passive"))
      (node (ref "C27") (pin "1") (pinfunction "1_1") (pintype "passive"))
      (node (ref "C29") (pin "1") (pinfunction "1_1") (pintype "passive"))
      (node (ref "C36") (pin "1") (pinfunction "1_1") (pintype "passive"))
      (node (ref "C37") (pin "1") (pinfunction "1_1") (pintype "passive"))
      (node (ref "C38") (pin "1") (pinfunction "1_1") (pintype "passive"))
      (node (ref "C39") (pin "1") (pinfunction "1_1") (pintype "passive"))
      (node (ref "C40") (pin "1") (pinfunction "1_1") (pintype "passive"))
      (node (ref "C43") (pin "1") (pinfunction "1_1") (pintype "passive"))
      (node (ref "L2") (pin "2") (pinfunction "2_2") (pintype "passive"))
      (node (ref "L7") (pin "1") (pinfunction "1_1") (pintype "passive"))
      (node (ref "R12") (pin "2") (pinfunction "2_2") (pintype "bidirectional"))
      (node (ref "R14") (pin "2") (pinfunction "2_2") (pintype "bidirectional"))
      (node (ref "U1") (pin "3A") (pinfunction "VDD_3A") (pintype "bidirectional"))
      (node (ref "U1") (pin "4C") (pinfunction "VDD_4C") (pintype "bidirectional"))
      (node (ref "U2") (pin "3A") (pinfunction "VDD_3A") (pintype "bidirectional"))
      (node (ref "U2") (pin "4C") (pinfunction "VDD_4C") (pintype "bidirectional"))
      (node (ref "U3") (pin "3A") (pinfunction "VDD_3A") (pintype "bidirectional"))
      (node (ref "U3") (pin "4C") (pinfunction "VDD_4C") (pintype "bidirectional"))
      (node (ref "U4") (pin "5") (pinfunction "BIAS_5") (pintype "bidirectional"))
      (node (ref "U5") (pin "1") (pinfunction "VIN_1") (pintype "bidirectional"))
      (node (ref "U5") (pin "3") (pinfunction "ON/~{OFF}_3") (pintype "bidirectional"))
      (node (ref "U6") (pin "3") (pinfunction "IN_3") (pintype "bidirectional"))
    )
    (net (code "3") (name "3V3_LDO") (class "Default")
      (node (ref "C42") (pin "1") (pinfunction "1_1") (pintype "passive"))
      (node (ref "U5") (pin "5") (pinfunction "VOUT_5") (pintype "bidirectional"))
      (node (ref "U7") (pin "1") (pinfunction "VIN_1") (pintype "bidirectional"))
      (node (ref "U8") (pin "3") (pinfunction "~{CE}_3") (pintype "bidirectional"))
    )
    (net (code "4") (name "3V3_STLINK") (class "Default")
      (node (ref "C45") (pin "1") (pinfunction "1_1") (pintype "passive"))
      (node (ref "C48") (pin "1") (pinfunction "1_1") (pintype "passive"))
      (node (ref "C49") (pin "1") (pinfunction "1_1") (pintype "passive"))
      (node (ref "C50") (pin "1") (pinfunction "1_1") (pintype "passive"))
      (node (ref "L3") (pin "1") (pinfunction "1_1") (pintype "passive"))
      (node (ref "R47") (pin "2") (pinfunction "2_2") (pintype "bidirectional"))
      (node (ref "U11") (pin "1") (pinfunction "~{EN}_1") (pintype "bidirectional"))
      (node (ref "U7") (pin "3") (pinfunction "~{CE}_3") (pintype "bidirectional"))
      (node (ref "U8") (pin "1") (pinfunction "VIN_1") (pintype "bidirectional"))
    )
    (net (code "5") (name "5V_CAN") (class "Default")
      (node (ref "C44") (pin "1") (pinfunction "1_1") (pintype "passive"))
      (node (ref "J6") (pin "1") (pinfunction "1_1") (pintype "bidirectional"))
      (node (ref "J7") (pin "1") (pinfunction "1_1") (pintype "bidirectional"))
      (node (ref "U6") (pin "4") (pinfunction "OUT_4") (pintype "bidirectional"))
    )
    (net (code "6") (name "BEMF_A") (class "Default")
      (node (ref "D9") (pin "A") (pinfunction "A_A") (pintype "passive"))
      (node (ref "R36") (pin "2") (pinfunction "2_2") (pintype "bidirectional"))
      (node (ref "R37") (pin "1") (pinfunction "1_1") (pintype "bidirectional"))
      (node (ref "U9") (pin "18") (pinfunction "PB2_18") (pintype "bidirectional"))
    )
    (net (code "7") (name "BEMF_B") (class "Default")
      (node (ref "D11") (pin "A") (pinfunction "A_A") (pintype "passive"))
      (node (ref "R38") (pin "2") (pinfunction "2_2") (pintype "bidirectional"))
      (node (ref "R39") (pin "1") (pinfunction "1_1") (pintype "bidirectional"))
      (node (ref "U9") (pin "12") (pinfunction "PA4_12") (pintype "bidirectional"))
    )
    (net (code "8") (name "BEMF_C") (class "Default")
      (node (ref "D13") (pin "A") (pinfunction "A_A") (pintype "passive"))
      (node (ref "R40") (pin "2") (pinfunction "2_2") (pintype "bidirectional"))
      (node (ref "R41") (pin "1") (pinfunction "1_1") (pintype "bidirectional"))
      (node (ref "U9") (pin "26") (pinfunction "PB12_26") (pintype "bidirectional"))
    )
    (net (code "9") (name "CAN_N") (class "Default")
      (node (ref "J6") (pin "3") (pinfunction "3_3") (pintype "bidirectional"))
      (node (ref "J7") (pin "3") (pinfunction "3_3") (pintype "bidirectional"))
      (node (ref "R48") (pin "1") (pinfunction "1_1") (pintype "bidirectional"))
      (node (ref "U12") (pin "6") (pinfunction "CANL_6") (pintype "bidirectional"))
    )
    (net (code "10") (name "CAN_P") (class "Default")
      (node (ref "J6") (pin "2") (pinfunction "2_2") (pintype "bidirectional"))
      (node (ref "J7") (pin "2") (pinfunction "2_2") (pintype "bidirectional"))
      (node (ref "R48") (pin "2") (pinfunction "2_2") (pintype "bidirectional"))
      (node (ref "U12") (pin "7") (pinfunction "CANH_7") (pintype "bidirectional"))
    )
    (net (code "11") (name "CAN_RX") (class "Default")
      (node (ref "U12") (pin "4") (pinfunction "RXD_4") (pintype "bidirectional"))
      (node (ref "U9") (pin "34") (pinfunction "PA12_34") (pintype "bidirectional"))
    )
    (net (code "12") (name "CAN_TX") (class "Default")
      (node (ref "U12") (pin "1") (pinfunction "TXD_1") (pintype "bidirectional"))
      (node (ref "U9") (pin "33") (pinfunction "PA11_33") (pintype "bidirectional"))
    )
    (net (code "13") (name "COM_RX") (class "Default")
      (node (ref "R22") (pin "1") (pinfunction "1_1") (pintype "bidirectional"))
      (node (ref "U11") (pin "9") (pinfunction "ROUT_9") (pintype "output"))
      (node (ref "U9") (pin "44") (pinfunction "PB7_44") (pintype "bidirectional"))
    )
    (net (code "14") (name "COM_TX") (class "Default")
      (node (ref "R23") (pin "1") (pinfunction "1_1") (pintype "bidirectional"))
      (node (ref "U11") (pin "11") (pinfunction "DIN_11") (pintype "input"))
      (node (ref "U9") (pin "43") (pinfunction "PB6_43") (pintype "bidirectional"))
    )
    (net (code "15") (name "CS_A_OUT") (class "Default")
      (node (ref "TP20") (pin "P$1") (pinfunction "P$1_P$1") (pintype "bidirectional"))
      (node (ref "U9") (pin "10") (pinfunction "PA2_10") (pintype "bidirectional"))
    )
    (net (code "16") (name "CS_B_OUT") (class "Default")
      (node (ref "TP21") (pin "P$1") (pinfunction "P$1_P$1") (pintype "bidirectional"))
      (node (ref "U9") (pin "14") (pinfunction "PA6_14") (pintype "bidirectional"))
    )
    (net (code "17") (name "CS_C_OUT") (class "Default")
      (node (ref "TP19") (pin "P$1") (pinfunction "P$1_P$1") (pintype "bidirectional"))
      (node (ref "U9") (pin "17") (pinfunction "PB1_17") (pintype "bidirectional"))
    )
    (net (code "18") (name "EN_CAN_PWR") (class "Default")
      (node (ref "U6") (pin "1") (pinfunction "EN_1") (pintype "bidirectional"))
    )
    (net (code "19") (name "FET_A_H") (class "Default")
      (node (ref "U1") (pin "4B") (pinfunction "HI_4B") (pintype "bidirectional"))
      (node (ref "U9") (pin "32") (pinfunction "PA10_32") (pintype "bidirectional"))
    )
    (net (code "20") (name "FET_A_L") (class "Default")
      (node (ref "U1") (pin "4A") (pinfunction "LI_4A") (pintype "bidirectional"))
      (node (ref "U9") (pin "29") (pinfunction "PB15_29") (pintype "bidirectional"))
    )
    (net (code "21") (name "FET_B_H") (class "Default")
      (node (ref "U2") (pin "4B") (pinfunction "HI_4B") (pintype "bidirectional"))
      (node (ref "U9") (pin "31") (pinfunction "PA9_31") (pintype "bidirectional"))
    )
    (net (code "22") (name "FET_B_L") (class "Default")
      (node (ref "U2") (pin "4A") (pinfunction "LI_4A") (pintype "bidirectional"))
      (node (ref "U9") (pin "28") (pinfunction "PB14_28") (pintype "bidirectional"))
    )
    (net (code "23") (name "FET_C_H") (class "Default")
      (node (ref "U3") (pin "4B") (pinfunction "HI_4B") (pintype "bidirectional"))
      (node (ref "U9") (pin "30") (pinfunction "PA8_30") (pintype "bidirectional"))
    )
    (net (code "24") (name "FET_C_L") (class "Default")
      (node (ref "U3") (pin "4A") (pinfunction "LI_4A") (pintype "bidirectional"))
      (node (ref "U9") (pin "27") (pinfunction "PB13_27") (pintype "bidirectional"))
    )
    (net (code "25") (name "GANFET_A_HOH") (class "Default")
      (node (ref "R1") (pin "1") (pinfunction "1_1") (pintype "bidirectional"))
      (node (ref "U1") (pin "2D") (pinfunction "HOH_2D") (pintype "bidirectional"))
    )
    (net (code "26") (name "GANFET_A_HOL") (class "Default")
      (node (ref "Q1") (pin "1") (pinfunction "G_1") (pintype "passive"))
      (node (ref "R1") (pin "2") (pinfunction "2_2") (pintype "bidirectional"))
      (node (ref "TP1") (pin "P$1") (pinfunction "P$1_P$1") (pintype "bidirectional"))
      (node (ref "U1") (pin "1D") (pinfunction "HOL_1D") (pintype "bidirectional"))
    )
    (net (code "27") (name "GANFET_A_HS") (class "Default")
      (node (ref "C26") (pin "2") (pinfunction "2_2") (pintype "passive"))
      (node (ref "D2") (pin "C") (pinfunction "C_C") (pintype "passive"))
      (node (ref "J3") (pin "1") (pinfunction "1_1") (pintype "bidirectional"))
      (node (ref "Q1") (pin "10") (pinfunction "S_10") (pintype "passive"))
      (node (ref "Q1") (pin "13") (pinfunction "S_13") (pintype "passive"))
      (node (ref "Q1") (pin "14") (pinfunction "S_14") (pintype "passive"))
      (node (ref "Q1") (pin "17") (pinfunction "S_17") (pintype "passive"))
      (node (ref "Q1") (pin "18") (pinfunction "S_18") (pintype "passive"))
      (node (ref "Q1") (pin "2") (pinfunction "S_2") (pintype "passive"))
      (node (ref "Q1") (pin "21") (pinfunction "S_21") (pintype "passive"))
      (node (ref "Q1") (pin "22") (pinfunction "S_22") (pintype "passive"))
      (node (ref "Q1") (pin "25") (pinfunction "S_25") (pintype "passive"))
      (node (ref "Q1") (pin "26") (pinfunction "S_26") (pintype "passive"))
      (node (ref "Q1") (pin "29") (pinfunction "S_29") (pintype "passive"))
      (node (ref "Q1") (pin "30") (pinfunction "S_30") (pintype "passive"))
      (node (ref "Q1") (pin "5") (pinfunction "S_5") (pintype "passive"))
      (node (ref "Q1") (pin "6") (pinfunction "S_6") (pintype "passive"))
      (node (ref "Q1") (pin "9") (pinfunction "S_9") (pintype "passive"))
      (node (ref "Q2") (pin "11") (pinfunction "D_11") (pintype "passive"))
      (node (ref "Q2") (pin "12") (pinfunction "D_12") (pintype "passive"))
      (node (ref "Q2") (pin "15") (pinfunction "D_15") (pintype "passive"))
      (node (ref "Q2") (pin "16") (pinfunction "D_16") (pintype "passive"))
      (node (ref "Q2") (pin "19") (pinfunction "D_19") (pintype "passive"))
      (node (ref "Q2") (pin "20") (pinfunction "D_20") (pintype "passive"))
      (node (ref "Q2") (pin "23") (pinfunction "D_23") (pintype "passive"))
      (node (ref "Q2") (pin "24") (pinfunction "D_24") (pintype "passive"))
      (node (ref "Q2") (pin "27") (pinfunction "D_27") (pintype "passive"))
      (node (ref "Q2") (pin "28") (pinfunction "D_28") (pintype "passive"))
      (node (ref "Q2") (pin "3") (pinfunction "D_3") (pintype "passive"))
      (node (ref "Q2") (pin "4") (pinfunction "D_4") (pintype "passive"))
      (node (ref "Q2") (pin "7") (pinfunction "D_7") (pintype "passive"))
      (node (ref "Q2") (pin "8") (pinfunction "D_8") (pintype "passive"))
      (node (ref "R36") (pin "1") (pinfunction "1_1") (pintype "bidirectional"))
      (node (ref "TP13") (pin "P$1") (pinfunction "P$1_P$1") (pintype "bidirectional"))
      (node (ref "U1") (pin "1C") (pinfunction "HS_1C") (pintype "bidirectional"))
      (node (ref "U1") (pin "4D") (pinfunction "HS_4D") (pintype "bidirectional"))
    )
    (net (code "28") (name "GANFET_A_LOH") (class "Default")
      (node (ref "R2") (pin "1") (pinfunction "1_1") (pintype "bidirectional"))
      (node (ref "U1") (pin "1B") (pinfunction "LOH_1B") (pintype "bidirectional"))
    )
    (net (code "29") (name "GANFET_A_LOL") (class "Default")
      (node (ref "Q2") (pin "1") (pinfunction "G_1") (pintype "passive"))
      (node (ref "R2") (pin "2") (pinfunction "2_2") (pintype "bidirectional"))
      (node (ref "TP2") (pin "P$1") (pinfunction "P$1_P$1") (pintype "bidirectional"))
      (node (ref "U1") (pin "1A") (pinfunction "LOL_1A") (pintype "bidirectional"))
    )
    (net (code "30") (name "GANFET_B_HOH") (class "Default")
      (node (ref "R4") (pin "1") (pinfunction "1_1") (pintype "bidirectional"))
      (node (ref "U2") (pin "2D") (pinfunction "HOH_2D") (pintype "bidirectional"))
    )
    (net (code "31") (name "GANFET_B_HOL") (class "Default")
      (node (ref "Q3") (pin "1") (pinfunction "G_1") (pintype "passive"))
      (node (ref "R4") (pin "2") (pinfunction "2_2") (pintype "bidirectional"))
      (node (ref "TP3") (pin "P$1") (pinfunction "P$1_P$1") (pintype "bidirectional"))
      (node (ref "U2") (pin "1D") (pinfunction "HOL_1D") (pintype "bidirectional"))
    )
    (net (code "32") (name "GANFET_B_HS") (class "Default")
      (node (ref "C28") (pin "2") (pinfunction "2_2") (pintype "passive"))
      (node (ref "D3") (pin "C") (pinfunction "C_C") (pintype "passive"))
      (node (ref "J4") (pin "1") (pinfunction "1_1") (pintype "bidirectional"))
      (node (ref "Q3") (pin "10") (pinfunction "S_10") (pintype "passive"))
      (node (ref "Q3") (pin "13") (pinfunction "S_13") (pintype "passive"))
      (node (ref "Q3") (pin "14") (pinfunction "S_14") (pintype "passive"))
      (node (ref "Q3") (pin "17") (pinfunction "S_17") (pintype "passive"))
      (node (ref "Q3") (pin "18") (pinfunction "S_18") (pintype "passive"))
      (node (ref "Q3") (pin "2") (pinfunction "S_2") (pintype "passive"))
      (node (ref "Q3") (pin "21") (pinfunction "S_21") (pintype "passive"))
      (node (ref "Q3") (pin "22") (pinfunction "S_22") (pintype "passive"))
      (node (ref "Q3") (pin "25") (pinfunction "S_25") (pintype "passive"))
      (node (ref "Q3") (pin "26") (pinfunction "S_26") (pintype "passive"))
      (node (ref "Q3") (pin "29") (pinfunction "S_29") (pintype "passive"))
      (node (ref "Q3") (pin "30") (pinfunction "S_30") (pintype "passive"))
      (node (ref "Q3") (pin "5") (pinfunction "S_5") (pintype "passive"))
      (node (ref "Q3") (pin "6") (pinfunction "S_6") (pintype "passive"))
      (node (ref "Q3") (pin "9") (pinfunction "S_9") (pintype "passive"))
      (node (ref "Q4") (pin "11") (pinfunction "D_11") (pintype "passive"))
      (node (ref "Q4") (pin "12") (pinfunction "D_12") (pintype "passive"))
      (node (ref "Q4") (pin "15") (pinfunction "D_15") (pintype "passive"))
      (node (ref "Q4") (pin "16") (pinfunction "D_16") (pintype "passive"))
      (node (ref "Q4") (pin "19") (pinfunction "D_19") (pintype "passive"))
      (node (ref "Q4") (pin "20") (pinfunction "D_20") (pintype "passive"))
      (node (ref "Q4") (pin "23") (pinfunction "D_23") (pintype "passive"))
      (node (ref "Q4") (pin "24") (pinfunction "D_24") (pintype "passive"))
      (node (ref "Q4") (pin "27") (pinfunction "D_27") (pintype "passive"))
      (node (ref "Q4") (pin "28") (pinfunction "D_28") (pintype "passive"))
      (node (ref "Q4") (pin "3") (pinfunction "D_3") (pintype "passive"))
      (node (ref "Q4") (pin "4") (pinfunction "D_4") (pintype "passive"))
      (node (ref "Q4") (pin "7") (pinfunction "D_7") (pintype "passive"))
      (node (ref "Q4") (pin "8") (pinfunction "D_8") (pintype "passive"))
      (node (ref "R38") (pin "1") (pinfunction "1_1") (pintype "bidirectional"))
      (node (ref "TP14") (pin "P$1") (pinfunction "P$1_P$1") (pintype "bidirectional"))
      (node (ref "U2") (pin "1C") (pinfunction "HS_1C") (pintype "bidirectional"))
      (node (ref "U2") (pin "4D") (pinfunction "HS_4D") (pintype "bidirectional"))
    )
    (net (code "33") (name "GANFET_B_LOH") (class "Default")
      (node (ref "R5") (pin "1") (pinfunction "1_1") (pintype "bidirectional"))
      (node (ref "U2") (pin "1B") (pinfunction "LOH_1B") (pintype "bidirectional"))
    )
    (net (code "34") (name "GANFET_B_LOL") (class "Default")
      (node (ref "Q4") (pin "1") (pinfunction "G_1") (pintype "passive"))
      (node (ref "R5") (pin "2") (pinfunction "2_2") (pintype "bidirectional"))
      (node (ref "TP4") (pin "P$1") (pinfunction "P$1_P$1") (pintype "bidirectional"))
      (node (ref "U2") (pin "1A") (pinfunction "LOL_1A") (pintype "bidirectional"))
    )
    (net (code "35") (name "GANFET_C_HOH") (class "Default")
      (node (ref "R7") (pin "1") (pinfunction "1_1") (pintype "bidirectional"))
      (node (ref "U3") (pin "2D") (pinfunction "HOH_2D") (pintype "bidirectional"))
    )
    (net (code "36") (name "GANFET_C_HOL") (class "Default")
      (node (ref "Q5") (pin "1") (pinfunction "G_1") (pintype "passive"))
      (node (ref "R7") (pin "2") (pinfunction "2_2") (pintype "bidirectional"))
      (node (ref "TP5") (pin "P$1") (pinfunction "P$1_P$1") (pintype "bidirectional"))
      (node (ref "U3") (pin "1D") (pinfunction "HOL_1D") (pintype "bidirectional"))
    )
    (net (code "37") (name "GANFET_C_HS") (class "Default")
      (node (ref "C30") (pin "2") (pinfunction "2_2") (pintype "passive"))
      (node (ref "D4") (pin "C") (pinfunction "C_C") (pintype "passive"))
      (node (ref "J5") (pin "1") (pinfunction "1_1") (pintype "bidirectional"))
      (node (ref "Q5") (pin "10") (pinfunction "S_10") (pintype "passive"))
      (node (ref "Q5") (pin "13") (pinfunction "S_13") (pintype "passive"))
      (node (ref "Q5") (pin "14") (pinfunction "S_14") (pintype "passive"))
      (node (ref "Q5") (pin "17") (pinfunction "S_17") (pintype "passive"))
      (node (ref "Q5") (pin "18") (pinfunction "S_18") (pintype "passive"))
      (node (ref "Q5") (pin "2") (pinfunction "S_2") (pintype "passive"))
      (node (ref "Q5") (pin "21") (pinfunction "S_21") (pintype "passive"))
      (node (ref "Q5") (pin "22") (pinfunction "S_22") (pintype "passive"))
      (node (ref "Q5") (pin "25") (pinfunction "S_25") (pintype "passive"))
      (node (ref "Q5") (pin "26") (pinfunction "S_26") (pintype "passive"))
      (node (ref "Q5") (pin "29") (pinfunction "S_29") (pintype "passive"))
      (node (ref "Q5") (pin "30") (pinfunction "S_30") (pintype "passive"))
      (node (ref "Q5") (pin "5") (pinfunction "S_5") (pintype "passive"))
      (node (ref "Q5") (pin "6") (pinfunction "S_6") (pintype "passive"))
      (node (ref "Q5") (pin "9") (pinfunction "S_9") (pintype "passive"))
      (node (ref "Q6") (pin "11") (pinfunction "D_11") (pintype "passive"))
      (node (ref "Q6") (pin "12") (pinfunction "D_12") (pintype "passive"))
      (node (ref "Q6") (pin "15") (pinfunction "D_15") (pintype "passive"))
      (node (ref "Q6") (pin "16") (pinfunction "D_16") (pintype "passive"))
      (node (ref "Q6") (pin "19") (pinfunction "D_19") (pintype "passive"))
      (node (ref "Q6") (pin "20") (pinfunction "D_20") (pintype "passive"))
      (node (ref "Q6") (pin "23") (pinfunction "D_23") (pintype "passive"))
      (node (ref "Q6") (pin "24") (pinfunction "D_24") (pintype "passive"))
      (node (ref "Q6") (pin "27") (pinfunction "D_27") (pintype "passive"))
      (node (ref "Q6") (pin "28") (pinfunction "D_28") (pintype "passive"))
      (node (ref "Q6") (pin "3") (pinfunction "D_3") (pintype "passive"))
      (node (ref "Q6") (pin "4") (pinfunction "D_4") (pintype "passive"))
      (node (ref "Q6") (pin "7") (pinfunction "D_7") (pintype "passive"))
      (node (ref "Q6") (pin "8") (pinfunction "D_8") (pintype "passive"))
      (node (ref "R40") (pin "1") (pinfunction "1_1") (pintype "bidirectional"))
      (node (ref "TP15") (pin "P$1") (pinfunction "P$1_P$1") (pintype "bidirectional"))
      (node (ref "U3") (pin "1C") (pinfunction "HS_1C") (pintype "bidirectional"))
      (node (ref "U3") (pin "4D") (pinfunction "HS_4D") (pintype "bidirectional"))
    )
    (net (code "38") (name "GANFET_C_LOH") (class "Default")
      (node (ref "R8") (pin "1") (pinfunction "1_1") (pintype "bidirectional"))
      (node (ref "U3") (pin "1B") (pinfunction "LOH_1B") (pintype "bidirectional"))
    )
    (net (code "39") (name "GANFET_C_LOL") (class "Default")
      (node (ref "Q6") (pin "1") (pinfunction "G_1") (pintype "passive"))
      (node (ref "R8") (pin "2") (pinfunction "2_2") (pintype "bidirectional"))
      (node (ref "TP6") (pin "P$1") (pinfunction "P$1_P$1") (pintype "bidirectional"))
      (node (ref "U3") (pin "1A") (pinfunction "LOL_1A") (pintype "bidirectional"))
    )
    (net (code "40") (name "GND") (class "Default")
      (node (ref "C1") (pin "-") (pinfunction "-_-") (pintype "passive"))
      (node (ref "C10") (pin "2") (pinfunction "2_2") (pintype "passive"))
      (node (ref "C11") (pin "2") (pinfunction "2_2") (pintype "passive"))
      (node (ref "C12") (pin "2") (pinfunction "2_2") (pintype "passive"))
      (node (ref "C13") (pin "2") (pinfunction "2_2") (pintype "passive"))
      (node (ref "C14") (pin "2") (pinfunction "2_2") (pintype "passive"))
      (node (ref "C15") (pin "2") (pinfunction "2_2") (pintype "passive"))
      (node (ref "C16") (pin "2") (pinfunction "2_2") (pintype "passive"))
      (node (ref "C17") (pin "2") (pinfunction "2_2") (pintype "passive"))
      (node (ref "C18") (pin "2") (pinfunction "2_2") (pintype "passive"))
      (node (ref "C19") (pin "2") (pinfunction "2_2") (pintype "passive"))
      (node (ref "C2") (pin "-") (pinfunction "-_-") (pintype "passive"))
      (node (ref "C20") (pin "2") (pinfunction "2_2") (pintype "passive"))
      (node (ref "C21") (pin "2") (pinfunction "2_2") (pintype "passive"))
      (node (ref "C22") (pin "2") (pinfunction "2_2") (pintype "passive"))
      (node (ref "C23") (pin "2") (pinfunction "2_2") (pintype "passive"))
      (node (ref "C24") (pin "2") (pinfunction "2_2") (pintype "passive"))
      (node (ref "C25") (pin "2") (pinfunction "2_2") (pintype "passive"))
      (node (ref "C27") (pin "2") (pinfunction "2_2") (pintype "passive"))
      (node (ref "C29") (pin "2") (pinfunction "2_2") (pintype "passive"))
      (node (ref "C3") (pin "-") (pinfunction "-_-") (pintype "passive"))
      (node (ref "C31") (pin "2") (pinfunction "2_2") (pintype "passive"))
      (node (ref "C32") (pin "2") (pinfunction "2_2") (pintype "passive"))
      (node (ref "C33") (pin "2") (pinfunction "2_2") (pintype "passive"))
      (node (ref "C34") (pin "2") (pinfunction "2_2") (pintype "passive"))
      (node (ref "C36") (pin "2") (pinfunction "2_2") (pintype "passive"))
      (node (ref "C38") (pin "2") (pinfunction "2_2") (pintype "passive"))
      (node (ref "C39") (pin "2") (pinfunction "2_2") (pintype "passive"))
      (node (ref "C4") (pin "2") (pinfunction "2_2") (pintype "passive"))
      (node (ref "C40") (pin "2") (pinfunction "2_2") (pintype "passive"))
      (node (ref "C41") (pin "2") (pinfunction "2_2") (pintype "passive"))
      (node (ref "C42") (pin "2") (pinfunction "2_2") (pintype "passive"))
      (node (ref "C43") (pin "2") (pinfunction "2_2") (pintype "passive"))
      (node (ref "C44") (pin "2") (pinfunction "2_2") (pintype "passive"))
      (node (ref "C45") (pin "2") (pinfunction "2_2") (pintype "passive"))
      (node (ref "C46") (pin "2") (pinfunction "2_2") (pintype "passive"))
      (node (ref "C47") (pin "2") (pinfunction "2_2") (pintype "passive"))
      (node (ref "C48") (pin "2") (pinfunction "2_2") (pintype "passive"))
      (node (ref "C49") (pin "2") (pinfunction "2_2") (pintype "passive"))
      (node (ref "C5") (pin "2") (pinfunction "2_2") (pintype "passive"))
      (node (ref "C50") (pin "2") (pinfunction "2_2") (pintype "passive"))
      (node (ref "C51") (pin "1") (pinfunction "1_1") (pintype "passive"))
      (node (ref "C52") (pin "1") (pinfunction "1_1") (pintype "passive"))
      (node (ref "C53") (pin "2") (pinfunction "2_2") (pintype "passive"))
      (node (ref "C54") (pin "2") (pinfunction "2_2") (pintype "passive"))
      (node (ref "C55") (pin "2") (pinfunction "2_2") (pintype "passive"))
      (node (ref "C56") (pin "2") (pinfunction "2_2") (pintype "passive"))
      (node (ref "C57") (pin "2") (pinfunction "2_2") (pintype "passive"))
      (node (ref "C58") (pin "2") (pinfunction "2_2") (pintype "passive"))
      (node (ref "C59") (pin "2") (pinfunction "2_2") (pintype "passive"))
      (node (ref "C6") (pin "2") (pinfunction "2_2") (pintype "passive"))
      (node (ref "C60") (pin "2") (pinfunction "2_2") (pintype "passive"))
      (node (ref "C61") (pin "2") (pinfunction "2_2") (pintype "passive"))
      (node (ref "C62") (pin "2") (pinfunction "2_2") (pintype "passive"))
      (node (ref "C63") (pin "2") (pinfunction "2_2") (pintype "passive"))
      (node (ref "C65") (pin "2") (pinfunction "2_2") (pintype "passive"))
      (node (ref "C66") (pin "2") (pinfunction "2_2") (pintype "passive"))
      (node (ref "C68") (pin "2") (pinfunction "2_2") (pintype "passive"))
      (node (ref "C69") (pin "2") (pinfunction "2_2") (pintype "passive"))
      (node (ref "C7") (pin "2") (pinfunction "2_2") (pintype "passive"))
      (node (ref "C70") (pin "2") (pinfunction "2_2") (pintype "passive"))
      (node (ref "C8") (pin "2") (pinfunction "2_2") (pintype "passive"))
      (node (ref "C9") (pin "2") (pinfunction "2_2") (pintype "passive"))
      (node (ref "D1") (pin "K") (pinfunction "C_K") (pintype "passive"))
      (node (ref "D2") (pin "A") (pinfunction "A_A") (pintype "passive"))
      (node (ref "D3") (pin "A") (pinfunction "A_A") (pintype "passive"))
      (node (ref "D4") (pin "A") (pinfunction "A_A") (pintype "passive"))
      (node (ref "D5") (pin "A") (pinfunction "A_A") (pintype "passive"))
      (node (ref "D6") (pin "A") (pinfunction "A_A") (pintype "passive"))
      (node (ref "D7") (pin "A") (pinfunction "A_A") (pintype "passive"))
      (node (ref "J2") (pin "1") (pinfunction "1_1") (pintype "bidirectional"))
      (node (ref "J6") (pin "4") (pinfunction "4_4") (pintype "bidirectional"))
      (node (ref "J6") (pin "5") (pinfunction "5_5") (pintype "bidirectional"))
      (node (ref "J6") (pin "6") (pinfunction "6_6") (pintype "bidirectional"))
      (node (ref "J7") (pin "4") (pinfunction "4_4") (pintype "bidirectional"))
      (node (ref "J7") (pin "5") (pinfunction "5_5") (pintype "bidirectional"))
      (node (ref "J7") (pin "6") (pinfunction "6_6") (pintype "bidirectional"))
      (node (ref "J8") (pin "4") (pinfunction "4_4") (pintype "bidirectional"))
      (node (ref "J8") (pin "5") (pinfunction "5_5") (pintype "bidirectional"))
      (node (ref "J8") (pin "6") (pinfunction "6_6") (pintype "bidirectional"))
      (node (ref "J9") (pin "3") (pinfunction "3_3") (pintype "bidirectional"))
      (node (ref "J9") (pin "5") (pinfunction "5_5") (pintype "bidirectional"))
      (node (ref "J9") (pin "7") (pinfunction "7_7") (pintype "bidirectional"))
      (node (ref "LED1") (pin "C") (pinfunction "C_C") (pintype "passive"))
      (node (ref "LED2") (pin "C") (pinfunction "C_C") (pintype "passive"))
      (node (ref "LED3") (pin "C") (pinfunction "C_C") (pintype "passive"))
      (node (ref "LED4") (pin "C") (pinfunction "C_C") (pintype "passive"))
      (node (ref "LED5") (pin "C") (pinfunction "C_C") (pintype "passive"))
      (node (ref "LED6") (pin "C") (pinfunction "C_C") (pintype "passive"))
      (node (ref "LED7") (pin "C") (pinfunction "C_C") (pintype "passive"))
      (node (ref "LED8") (pin "C") (pinfunction "C_C") (pintype "passive"))
      (node (ref "R11") (pin "1") (pinfunction "1_1") (pintype "bidirectional"))
      (node (ref "R13") (pin "1") (pinfunction "1_1") (pintype "bidirectional"))
      (node (ref "R24") (pin "1") (pinfunction "1_1") (pintype "bidirectional"))
      (node (ref "R28") (pin "1") (pinfunction "1_1") (pintype "bidirectional"))
      (node (ref "R3") (pin "2") (pinfunction "2_2") (pintype "passive"))
      (node (ref "R31") (pin "1") (pinfunction "1_1") (pintype "bidirectional"))
      (node (ref "R34") (pin "1") (pinfunction "1_1") (pintype "bidirectional"))
      (node (ref "R35") (pin "1") (pinfunction "1_1") (pintype "bidirectional"))
      (node (ref "R47") (pin "1") (pinfunction "1_1") (pintype "bidirectional"))
      (node (ref "R6") (pin "2") (pinfunction "2_2") (pintype "passive"))
      (node (ref "R9") (pin "2") (pinfunction "2_2") (pintype "passive"))
      (node (ref "TP10") (pin "P$1") (pinfunction "P$1_P$1") (pintype "bidirectional"))
      (node (ref "TP11") (pin "P$1") (pinfunction "P$1_P$1") (pintype "bidirectional"))
      (node (ref "TP12") (pin "P$1") (pinfunction "P$1_P$1") (pintype "bidirectional"))
      (node (ref "TP16") (pin "P$1") (pinfunction "P$1_P$1") (pintype "bidirectional"))
      (node (ref "TP17") (pin "P$1") (pinfunction "P$1_P$1") (pintype "bidirectional"))
      (node (ref "TP18") (pin "P$1") (pinfunction "P$1_P$1") (pintype "bidirectional"))
      (node (ref "TP22") (pin "P$1") (pinfunction "P$1_P$1") (pintype "bidirectional"))
      (node (ref "TP23") (pin "P$1") (pinfunction "P$1_P$1") (pintype "bidirectional"))
      (node (ref "TP24") (pin "P$1") (pinfunction "P$1_P$1") (pintype "bidirectional"))
      (node (ref "TP26") (pin "P$1") (pinfunction "P$1_P$1") (pintype "bidirectional"))
      (node (ref "TP36") (pin "P$1") (pinfunction "P$1_P$1") (pintype "bidirectional"))
      (node (ref "TP7") (pin "P$1") (pinfunction "P$1_P$1") (pintype "bidirectional"))
      (node (ref "TP8") (pin "P$1") (pinfunction "P$1_P$1") (pintype "bidirectional"))
      (node (ref "TP9") (pin "P$1") (pinfunction "P$1_P$1") (pintype "bidirectional"))
      (node (ref "U1") (pin "2A") (pinfunction "VSS_2A") (pintype "bidirectional"))
      (node (ref "U10") (pin "2") (pinfunction "GND_2") (pintype "bidirectional"))
      (node (ref "U11") (pin "12") (pinfunction "FORCEON_12") (pintype "bidirectional"))
      (node (ref "U11") (pin "14") (pinfunction "GND_14") (pintype "passive"))
      (node (ref "U12") (pin "2") (pinfunction "GND_2") (pintype "bidirectional"))
      (node (ref "U2") (pin "2A") (pinfunction "VSS_2A") (pintype "bidirectional"))
      (node (ref "U3") (pin "2A") (pinfunction "VSS_2A") (pintype "bidirectional"))
      (node (ref "U4") (pin "10") (pinfunction "AGND_10") (pintype "bidirectional"))
      (node (ref "U4") (pin "15") (pinfunction "PGND_15") (pintype "bidirectional"))
      (node (ref "U4") (pin "16") (pinfunction "PGND_16") (pintype "bidirectional"))
      (node (ref "U4") (pin "6") (pinfunction "SYNC_6") (pintype "bidirectional"))
      (node (ref "U4") (pin "PAD") (pinfunction "PGND_PAD") (pintype "bidirectional"))
      (node (ref "U5") (pin "2") (pinfunction "GND_2") (pintype "bidirectional"))
      (node (ref "U6") (pin "2") (pinfunction "GND_2") (pintype "bidirectional"))
      (node (ref "U6") (pin "5") (pinfunction "D1_5") (pintype "bidirectional"))
      (node (ref "U6") (pin "6") (pinfunction "D2_6") (pintype "bidirectional"))
      (node (ref "U7") (pin "2") (pinfunction "GND_2") (pintype "bidirectional"))
      (node (ref "U7") (pin "4") (pinfunction "GND_4") (pintype "bidirectional"))
      (node (ref "U8") (pin "2") (pinfunction "GND_2") (pintype "bidirectional"))
      (node (ref "U8") (pin "4") (pinfunction "GND_4") (pintype "bidirectional"))
      (node (ref "U9") (pin "19") (pinfunction "VSSA_19") (pintype "bidirectional"))
      (node (ref "U9") (pin "23") (pinfunction "VSS4_23") (pintype "bidirectional"))
      (node (ref "U9") (pin "35") (pinfunction "VSS6_35") (pintype "bidirectional"))
      (node (ref "U9") (pin "47") (pinfunction "VSS8_47") (pintype "bidirectional"))
      (node (ref "Y1") (pin "2") (pinfunction "3_2") (pintype "passive"))
      (node (ref "Y1") (pin "4") (pinfunction "3_4") (pintype "passive"))
    )
    (net (code "41") (name "GPIO_BEMF") (class "Default")
      (node (ref "D10") (pin "C") (pinfunction "C_C") (pintype "passive"))
      (node (ref "D12") (pin "C") (pinfunction "C_C") (pintype "passive"))
      (node (ref "D14") (pin "C") (pinfunction "C_C") (pintype "passive"))
      (node (ref "U9") (pin "39") (pinfunction "PA15_39") (pintype "bidirectional"))
    )
    (net (code "42") (name "LED1") (class "Default")
      (node (ref "R42") (pin "2") (pinfunction "2_2") (pintype "bidirectional"))
      (node (ref "U9") (pin "42") (pinfunction "PB5_42") (pintype "bidirectional"))
    )
    (net (code "43") (name "LED2") (class "Default")
      (node (ref "R43") (pin "2") (pinfunction "2_2") (pintype "bidirectional"))
      (node (ref "U9") (pin "46") (pinfunction "PB9_46") (pintype "bidirectional"))
    )
    (net (code "44") (name "LED3") (class "Default")
      (node (ref "R44") (pin "2") (pinfunction "2_2") (pintype "bidirectional"))
      (node (ref "U9") (pin "2") (pinfunction "PC13_2") (pintype "bidirectional"))
    )
    (net (code "45") (name "LED4") (class "Default")
      (node (ref "R45") (pin "2") (pinfunction "2_2") (pintype "bidirectional"))
      (node (ref "U9") (pin "3") (pinfunction "PC14-OSC32_IN_3") (pintype "bidirectional"))
    )
    (net (code "46") (name "LED5") (class "Default")
      (node (ref "R46") (pin "2") (pinfunction "2_2") (pintype "bidirectional"))
      (node (ref "U9") (pin "4") (pinfunction "PC15-OSC32_OUT_4") (pintype "bidirectional"))
    )
    (net (code "47") (name "Net-(C32-Pad1)") (class "Default")
      (node (ref "C32") (pin "1") (pinfunction "1_1") (pintype "passive"))
      (node (ref "L1") (pin "2") (pinfunction "2_2") (pintype "passive"))
      (node (ref "R10") (pin "2") (pinfunction "2_2") (pintype "bidirectional"))
      (node (ref "U4") (pin "13") (pinfunction "VIN_13") (pintype "bidirectional"))
      (node (ref "U4") (pin "14") (pinfunction "VIN_14") (pintype "bidirectional"))
    )
    (net (code "48") (name "Net-(C35-Pad1)") (class "Default")
      (node (ref "C35") (pin "1") (pinfunction "1_1") (pintype "passive"))
      (node (ref "L2") (pin "1") (pinfunction "1_1") (pintype "passive"))
      (node (ref "U4") (pin "1") (pinfunction "SW_1") (pintype "bidirectional"))
      (node (ref "U4") (pin "2") (pinfunction "SW_2") (pintype "bidirectional"))
    )
    (net (code "49") (name "Net-(D6-PadC)") (class "Default")
      (node (ref "D6") (pin "C") (pinfunction "C_C") (pintype "passive"))
      (node (ref "J9") (pin "1") (pinfunction "1_1") (pintype "bidirectional"))
      (node (ref "L3") (pin "2") (pinfunction "2_2") (pintype "passive"))
    )
    (net (code "50") (name "Net-(D10-PadA)") (class "Default")
      (node (ref "D10") (pin "A") (pinfunction "A_A") (pintype "passive"))
      (node (ref "R37") (pin "2") (pinfunction "2_2") (pintype "bidirectional"))
    )
    (net (code "51") (name "Net-(D12-PadA)") (class "Default")
      (node (ref "D12") (pin "A") (pinfunction "A_A") (pintype "passive"))
      (node (ref "R39") (pin "2") (pinfunction "2_2") (pintype "bidirectional"))
    )
    (net (code "52") (name "Net-(D14-PadA)") (class "Default")
      (node (ref "D14") (pin "A") (pinfunction "A_A") (pintype "passive"))
      (node (ref "R41") (pin "2") (pinfunction "2_2") (pintype "bidirectional"))
    )
    (net (code "53") (name "Net-(J8-Pad1)") (class "Default")
      (node (ref "J8") (pin "1") (pinfunction "1_1") (pintype "bidirectional"))
      (node (ref "R21") (pin "2") (pinfunction "2_2") (pintype "bidirectional"))
    )
    (net (code "54") (name "Net-(J9-Pad9)") (class "Default")
      (node (ref "J9") (pin "9") (pinfunction "9_9") (pintype "bidirectional"))
      (node (ref "R22") (pin "2") (pinfunction "2_2") (pintype "bidirectional"))
    )
    (net (code "55") (name "Net-(J9-Pad10)") (class "Default")
      (node (ref "J9") (pin "10") (pinfunction "10_10") (pintype "bidirectional"))
      (node (ref "R23") (pin "2") (pinfunction "2_2") (pintype "bidirectional"))
    )
    (net (code "56") (name "Net-(LED1-PadA)") (class "Default")
      (node (ref "LED1") (pin "A") (pinfunction "A_A") (pintype "passive"))
      (node (ref "R14") (pin "1") (pinfunction "1_1") (pintype "bidirectional"))
    )
    (net (code "57") (name "Net-(LED2-PadA)") (class "Default")
      (node (ref "LED2") (pin "A") (pinfunction "A_A") (pintype "passive"))
      (node (ref "R17") (pin "1") (pinfunction "1_1") (pintype "bidirectional"))
    )
    (net (code "58") (name "Net-(LED3-PadA)") (class "Default")
      (node (ref "LED3") (pin "A") (pinfunction "A_A") (pintype "passive"))
      (node (ref "R20") (pin "1") (pinfunction "1_1") (pintype "bidirectional"))
    )
    (net (code "59") (name "Net-(LED4-PadA)") (class "Default")
      (node (ref "LED4") (pin "A") (pinfunction "A_A") (pintype "passive"))
      (node (ref "R42") (pin "1") (pinfunction "1_1") (pintype "bidirectional"))
    )
    (net (code "60") (name "Net-(LED5-PadA)") (class "Default")
      (node (ref "LED5") (pin "A") (pinfunction "A_A") (pintype "passive"))
      (node (ref "R43") (pin "1") (pinfunction "1_1") (pintype "bidirectional"))
    )
    (net (code "61") (name "Net-(LED6-PadA)") (class "Default")
      (node (ref "LED6") (pin "A") (pinfunction "A_A") (pintype "passive"))
      (node (ref "R44") (pin "1") (pinfunction "1_1") (pintype "bidirectional"))
    )
    (net (code "62") (name "Net-(LED7-PadA)") (class "Default")
      (node (ref "LED7") (pin "A") (pinfunction "A_A") (pintype "passive"))
      (node (ref "R45") (pin "1") (pinfunction "1_1") (pintype "bidirectional"))
    )
    (net (code "63") (name "Net-(LED8-PadA)") (class "Default")
      (node (ref "LED8") (pin "A") (pinfunction "A_A") (pintype "passive"))
      (node (ref "R46") (pin "1") (pinfunction "1_1") (pintype "bidirectional"))
    )
    (net (code "64") (name "Net-(Q2-S-Pad10)") (class "Default")
      (node (ref "Q2") (pin "10") (pinfunction "S_10") (pintype "passive"))
      (node (ref "Q2") (pin "13") (pinfunction "S_13") (pintype "passive"))
      (node (ref "Q2") (pin "14") (pinfunction "S_14") (pintype "passive"))
      (node (ref "Q2") (pin "17") (pinfunction "S_17") (pintype "passive"))
      (node (ref "Q2") (pin "18") (pinfunction "S_18") (pintype "passive"))
      (node (ref "Q2") (pin "2") (pinfunction "S_2") (pintype "passive"))
      (node (ref "Q2") (pin "21") (pinfunction "S_21") (pintype "passive"))
      (node (ref "Q2") (pin "22") (pinfunction "S_22") (pintype "passive"))
      (node (ref "Q2") (pin "25") (pinfunction "S_25") (pintype "passive"))
      (node (ref "Q2") (pin "26") (pinfunction "S_26") (pintype "passive"))
      (node (ref "Q2") (pin "29") (pinfunction "S_29") (pintype "passive"))
      (node (ref "Q2") (pin "30") (pinfunction "S_30") (pintype "passive"))
      (node (ref "Q2") (pin "5") (pinfunction "S_5") (pintype "passive"))
      (node (ref "Q2") (pin "6") (pinfunction "S_6") (pintype "passive"))
      (node (ref "Q2") (pin "9") (pinfunction "S_9") (pintype "passive"))
      (node (ref "R3") (pin "1") (pinfunction "1_1") (pintype "passive"))
    )
    (net (code "65") (name "Net-(Q4-S-Pad10)") (class "Default")
      (node (ref "Q4") (pin "10") (pinfunction "S_10") (pintype "passive"))
      (node (ref "Q4") (pin "13") (pinfunction "S_13") (pintype "passive"))
      (node (ref "Q4") (pin "14") (pinfunction "S_14") (pintype "passive"))
      (node (ref "Q4") (pin "17") (pinfunction "S_17") (pintype "passive"))
      (node (ref "Q4") (pin "18") (pinfunction "S_18") (pintype "passive"))
      (node (ref "Q4") (pin "2") (pinfunction "S_2") (pintype "passive"))
      (node (ref "Q4") (pin "21") (pinfunction "S_21") (pintype "passive"))
      (node (ref "Q4") (pin "22") (pinfunction "S_22") (pintype "passive"))
      (node (ref "Q4") (pin "25") (pinfunction "S_25") (pintype "passive"))
      (node (ref "Q4") (pin "26") (pinfunction "S_26") (pintype "passive"))
      (node (ref "Q4") (pin "29") (pinfunction "S_29") (pintype "passive"))
      (node (ref "Q4") (pin "30") (pinfunction "S_30") (pintype "passive"))
      (node (ref "Q4") (pin "5") (pinfunction "S_5") (pintype "passive"))
      (node (ref "Q4") (pin "6") (pinfunction "S_6") (pintype "passive"))
      (node (ref "Q4") (pin "9") (pinfunction "S_9") (pintype "passive"))
      (node (ref "R6") (pin "1") (pinfunction "1_1") (pintype "passive"))
    )
    (net (code "66") (name "Net-(Q6-S-Pad10)") (class "Default")
      (node (ref "Q6") (pin "10") (pinfunction "S_10") (pintype "passive"))
      (node (ref "Q6") (pin "13") (pinfunction "S_13") (pintype "passive"))
      (node (ref "Q6") (pin "14") (pinfunction "S_14") (pintype "passive"))
      (node (ref "Q6") (pin "17") (pinfunction "S_17") (pintype "passive"))
      (node (ref "Q6") (pin "18") (pinfunction "S_18") (pintype "passive"))
      (node (ref "Q6") (pin "2") (pinfunction "S_2") (pintype "passive"))
      (node (ref "Q6") (pin "21") (pinfunction "S_21") (pintype "passive"))
      (node (ref "Q6") (pin "22") (pinfunction "S_22") (pintype "passive"))
      (node (ref "Q6") (pin "25") (pinfunction "S_25") (pintype "passive"))
      (node (ref "Q6") (pin "26") (pinfunction "S_26") (pintype "passive"))
      (node (ref "Q6") (pin "29") (pinfunction "S_29") (pintype "passive"))
      (node (ref "Q6") (pin "30") (pinfunction "S_30") (pintype "passive"))
      (node (ref "Q6") (pin "5") (pinfunction "S_5") (pintype "passive"))
      (node (ref "Q6") (pin "6") (pinfunction "S_6") (pintype "passive"))
      (node (ref "Q6") (pin "9") (pinfunction "S_9") (pintype "passive"))
      (node (ref "R9") (pin "1") (pinfunction "1_1") (pintype "passive"))
    )
    (net (code "67") (name "Net-(Q7A-D)") (class "Default")
      (node (ref "Q7") (pin "3") (pinfunction "D_3") (pintype "passive"))
      (node (ref "R17") (pin "2") (pinfunction "2_2") (pintype "bidirectional"))
    )
    (net (code "68") (name "Net-(Q7A-G)") (class "Default")
      (node (ref "Q7") (pin "2") (pinfunction "G_2") (pintype "passive"))
      (node (ref "R15") (pin "1") (pinfunction "1_1") (pintype "bidirectional"))
      (node (ref "R16") (pin "2") (pinfunction "2_2") (pintype "bidirectional"))
    )
    (net (code "69") (name "Net-(Q7B-D)") (class "Default")
      (node (ref "Q7") (pin "6") (pinfunction "D_6") (pintype "passive"))
      (node (ref "R20") (pin "2") (pinfunction "2_2") (pintype "bidirectional"))
    )
    (net (code "70") (name "Net-(Q7B-G)") (class "Default")
      (node (ref "Q7") (pin "5") (pinfunction "G_5") (pintype "passive"))
      (node (ref "R18") (pin "1") (pinfunction "1_1") (pintype "bidirectional"))
      (node (ref "R19") (pin "2") (pinfunction "2_2") (pintype "bidirectional"))
    )
    (net (code "71") (name "Net-(U1-HB)") (class "Default")
      (node (ref "C26") (pin "1") (pinfunction "1_1") (pintype "passive"))
      (node (ref "U1") (pin "3D") (pinfunction "HB_3D") (pintype "bidirectional"))
    )
    (net (code "72") (name "Net-(U2-HB)") (class "Default")
      (node (ref "C28") (pin "1") (pinfunction "1_1") (pintype "passive"))
      (node (ref "U2") (pin "3D") (pinfunction "HB_3D") (pintype "bidirectional"))
    )
    (net (code "73") (name "Net-(U3-HB)") (class "Default")
      (node (ref "C30") (pin "1") (pinfunction "1_1") (pintype "passive"))
      (node (ref "U3") (pin "3D") (pinfunction "HB_3D") (pintype "bidirectional"))
    )
    (net (code "74") (name "Net-(U4-CBOOT)") (class "Default")
      (node (ref "C35") (pin "2") (pinfunction "2_2") (pintype "passive"))
      (node (ref "U4") (pin "3") (pinfunction "CBOOT_3") (pintype "bidirectional"))
    )
    (net (code "75") (name "Net-(U4-ENABLE)") (class "Default")
      (node (ref "R10") (pin "1") (pinfunction "1_1") (pintype "bidirectional"))
      (node (ref "R11") (pin "2") (pinfunction "2_2") (pintype "bidirectional"))
      (node (ref "U4") (pin "12") (pinfunction "ENABLE_12") (pintype "bidirectional"))
    )
    (net (code "76") (name "Net-(U4-FB)") (class "Default")
      (node (ref "C37") (pin "2") (pinfunction "2_2") (pintype "passive"))
      (node (ref "R12") (pin "1") (pinfunction "1_1") (pintype "bidirectional"))
      (node (ref "R13") (pin "2") (pinfunction "2_2") (pintype "bidirectional"))
      (node (ref "U4") (pin "9") (pinfunction "FB_9") (pintype "bidirectional"))
    )
    (net (code "77") (name "Net-(U4-SS{slash}TRK)") (class "Default")
      (node (ref "C33") (pin "1") (pinfunction "1_1") (pintype "passive"))
      (node (ref "U4") (pin "11") (pinfunction "SS/TRK_11") (pintype "bidirectional"))
    )
    (net (code "78") (name "Net-(U4-VCC)") (class "Default")
      (node (ref "C34") (pin "1") (pinfunction "1_1") (pintype "passive"))
      (node (ref "U4") (pin "4") (pinfunction "VCC_4") (pintype "bidirectional"))
    )
    (net (code "79") (name "Net-(U5-BYPASS)") (class "Default")
      (node (ref "C41") (pin "1") (pinfunction "1_1") (pintype "passive"))
      (node (ref "U5") (pin "4") (pinfunction "BYPASS_4") (pintype "bidirectional"))
    )
    (net (code "80") (name "Net-(U9-PA0)") (class "Default")
      (node (ref "D7") (pin "C") (pinfunction "C_C") (pintype "passive"))
      (node (ref "D8") (pin "A") (pinfunction "A_A") (pintype "passive"))
      (node (ref "R24") (pin "2") (pinfunction "2_2") (pintype "bidirectional"))
      (node (ref "R25") (pin "1") (pinfunction "1_1") (pintype "bidirectional"))
      (node (ref "U9") (pin "8") (pinfunction "PA0_8") (pintype "bidirectional"))
    )
    (net (code "81") (name "Net-(U9-PA1)") (class "Default")
      (node (ref "R26") (pin "2") (pinfunction "2_2") (pintype "bidirectional"))
      (node (ref "R27") (pin "1") (pinfunction "1_1") (pintype "bidirectional"))
      (node (ref "R28") (pin "2") (pinfunction "2_2") (pintype "bidirectional"))
      (node (ref "U9") (pin "9") (pinfunction "PA1_9") (pintype "bidirectional"))
    )
    (net (code "82") (name "Net-(U9-PA7)") (class "Default")
      (node (ref "R29") (pin "2") (pinfunction "2_2") (pintype "bidirectional"))
      (node (ref "R30") (pin "1") (pinfunction "1_1") (pintype "bidirectional"))
      (node (ref "R31") (pin "2") (pinfunction "2_2") (pintype "bidirectional"))
      (node (ref "U9") (pin "15") (pinfunction "PA7_15") (pintype "bidirectional"))
    )
    (net (code "83") (name "Net-(U9-PB0)") (class "Default")
      (node (ref "R32") (pin "2") (pinfunction "2_2") (pintype "bidirectional"))
      (node (ref "R33") (pin "1") (pinfunction "1_1") (pintype "bidirectional"))
      (node (ref "R34") (pin "2") (pinfunction "2_2") (pintype "bidirectional"))
      (node (ref "U9") (pin "16") (pinfunction "PB0_16") (pintype "bidirectional"))
    )
    (net (code "84") (name "Net-(U9-PB8-BOOT0)") (class "Default")
      (node (ref "R35") (pin "2") (pinfunction "2_2") (pintype "bidirectional"))
      (node (ref "U9") (pin "45") (pinfunction "PB8-BOOT0_45") (pintype "bidirectional"))
    )
    (net (code "85") (name "Net-(U9-PF0-OSC_IN)") (class "Default")
      (node (ref "C51") (pin "2") (pinfunction "2_2") (pintype "passive"))
      (node (ref "U9") (pin "5") (pinfunction "PF0-OSC_IN_5") (pintype "bidirectional"))
      (node (ref "Y1") (pin "1") (pinfunction "1_1") (pintype "passive"))
    )
    (net (code "86") (name "Net-(U9-PF1-OSC_OUT)") (class "Default")
      (node (ref "C52") (pin "2") (pinfunction "2_2") (pintype "passive"))
      (node (ref "U9") (pin "6") (pinfunction "PF1-OSC_OUT_6") (pintype "bidirectional"))
      (node (ref "Y1") (pin "3") (pinfunction "2_3") (pintype "passive"))
    )
    (net (code "87") (name "Net-(U9-VBAT)") (class "Default")
      (node (ref "C57") (pin "1") (pinfunction "1_1") (pintype "passive"))
      (node (ref "C58") (pin "1") (pinfunction "1_1") (pintype "passive"))
      (node (ref "C59") (pin "1") (pinfunction "1_1") (pintype "passive"))
      (node (ref "C60") (pin "1") (pinfunction "1_1") (pintype "passive"))
      (node (ref "L5") (pin "1") (pinfunction "1_1") (pintype "passive"))
      (node (ref "U9") (pin "1") (pinfunction "VBAT_1") (pintype "bidirectional"))
      (node (ref "U9") (pin "24") (pinfunction "VDD4_24") (pintype "bidirectional"))
      (node (ref "U9") (pin "36") (pinfunction "VDD6_36") (pintype "bidirectional"))
      (node (ref "U9") (pin "48") (pinfunction "VDD8_48") (pintype "bidirectional"))
    )
    (net (code "88") (name "Net-(U9-VDDA)") (class "Default")
      (node (ref "C53") (pin "1") (pinfunction "1_1") (pintype "passive"))
      (node (ref "C55") (pin "1") (pinfunction "1_1") (pintype "passive"))
      (node (ref "L4") (pin "2") (pinfunction "2_2") (pintype "passive"))
      (node (ref "U9") (pin "21") (pinfunction "VDDA_21") (pintype "bidirectional"))
    )
    (net (code "89") (name "Net-(U9-VREF)") (class "Default")
      (node (ref "C54") (pin "1") (pinfunction "1_1") (pintype "passive"))
      (node (ref "C56") (pin "1") (pinfunction "1_1") (pintype "passive"))
      (node (ref "U9") (pin "20") (pinfunction "VREF_20") (pintype "bidirectional"))
    )
    (net (code "90") (name "Net-(U11-C1+)") (class "Default")
      (node (ref "C64") (pin "1") (pinfunction "1_1") (pintype "passive"))
      (node (ref "U11") (pin "2") (pinfunction "C1+_2") (pintype "passive"))
    )
    (net (code "91") (name "Net-(U11-C1-)") (class "Default")
      (node (ref "C64") (pin "2") (pinfunction "2_2") (pintype "passive"))
      (node (ref "U11") (pin "4") (pinfunction "C1-_4") (pintype "passive"))
    )
    (net (code "92") (name "Net-(U11-C2+)") (class "Default")
      (node (ref "C67") (pin "1") (pinfunction "1_1") (pintype "passive"))
      (node (ref "U11") (pin "5") (pinfunction "C2+_5") (pintype "passive"))
    )
    (net (code "93") (name "Net-(U11-C2-)") (class "Default")
      (node (ref "C67") (pin "2") (pinfunction "2_2") (pintype "passive"))
      (node (ref "U11") (pin "6") (pinfunction "C2-_6") (pintype "passive"))
    )
    (net (code "94") (name "Net-(U11-V+)") (class "Default")
      (node (ref "C65") (pin "1") (pinfunction "1_1") (pintype "passive"))
      (node (ref "U11") (pin "3") (pinfunction "V+_3") (pintype "power_in"))
    )
    (net (code "95") (name "Net-(U11-V-)") (class "Default")
      (node (ref "C66") (pin "1") (pinfunction "1_1") (pintype "passive"))
      (node (ref "U11") (pin "7") (pinfunction "V-_7") (pintype "power_in"))
    )
    (net (code "96") (name "Net-(U12-VCC)") (class "Default")
      (node (ref "C68") (pin "1") (pinfunction "1_1") (pintype "passive"))
      (node (ref "C69") (pin "1") (pinfunction "1_1") (pintype "passive"))
      (node (ref "L7") (pin "2") (pinfunction "2_2") (pintype "passive"))
      (node (ref "U12") (pin "3") (pinfunction "VCC_3") (pintype "bidirectional"))
    )
    (net (code "97") (name "Net-(U12-VIO)") (class "Default")
      (node (ref "C70") (pin "1") (pinfunction "1_1") (pintype "passive"))
      (node (ref "L8") (pin "1") (pinfunction "1_1") (pintype "passive"))
      (node (ref "U12") (pin "5") (pinfunction "VIO_5") (pintype "bidirectional"))
    )
    (net (code "98") (name "RC_PWM_IN") (class "Default")
      (node (ref "D5") (pin "C") (pinfunction "C_C") (pintype "passive"))
      (node (ref "R21") (pin "1") (pinfunction "1_1") (pintype "bidirectional"))
      (node (ref "TP39") (pin "P$1") (pinfunction "P$1_P$1") (pintype "bidirectional"))
      (node (ref "U9") (pin "41") (pinfunction "PB4_41") (pintype "bidirectional"))
    )
    (net (code "99") (name "RS232_RX") (class "Default")
      (node (ref "J8") (pin "3") (pinfunction "3_3") (pintype "bidirectional"))
      (node (ref "U11") (pin "8") (pinfunction "RIN_8") (pintype "input"))
    )
    (net (code "100") (name "RS232_TX") (class "Default")
      (node (ref "J8") (pin "2") (pinfunction "2_2") (pintype "bidirectional"))
      (node (ref "U11") (pin "13") (pinfunction "DOUT_13") (pintype "output"))
    )
    (net (code "101") (name "RS232_VCC") (class "Default")
      (node (ref "C62") (pin "1") (pinfunction "1_1") (pintype "passive"))
      (node (ref "C63") (pin "1") (pinfunction "1_1") (pintype "passive"))
      (node (ref "L6") (pin "2") (pinfunction "2_2") (pintype "passive"))
      (node (ref "U11") (pin "15") (pinfunction "VCC_15") (pintype "power_in"))
      (node (ref "U11") (pin "16") (pinfunction "~{FORCEOFF}_16") (pintype "bidirectional"))
    )
    (net (code "102") (name "SHUNT_A+") (class "Default")
      (node (ref "R26") (pin "1") (pinfunction "1_1") (pintype "bidirectional"))
      (node (ref "R3") (pin "1_SENSE") (pinfunction "1K_1_SENSE") (pintype "passive"))
    )
    (net (code "103") (name "SHUNT_A-") (class "Default")
      (node (ref "R3") (pin "2_SENSE") (pinfunction "2K_2_SENSE") (pintype "passive"))
      (node (ref "U9") (pin "11") (pinfunction "PA3_11") (pintype "bidirectional"))
    )
    (net (code "104") (name "SHUNT_B+") (class "Default")
      (node (ref "R29") (pin "1") (pinfunction "1_1") (pintype "bidirectional"))
      (node (ref "R6") (pin "1_SENSE") (pinfunction "1K_1_SENSE") (pintype "passive"))
    )
    (net (code "105") (name "SHUNT_B-") (class "Default")
      (node (ref "R6") (pin "2_SENSE") (pinfunction "2K_2_SENSE") (pintype "passive"))
      (node (ref "U9") (pin "13") (pinfunction "PA5_13") (pintype "bidirectional"))
    )
    (net (code "106") (name "SHUNT_C+") (class "Default")
      (node (ref "R32") (pin "1") (pinfunction "1_1") (pintype "bidirectional"))
      (node (ref "R9") (pin "1_SENSE") (pinfunction "1K_1_SENSE") (pintype "passive"))
    )
    (net (code "107") (name "SHUNT_C-") (class "Default")
      (node (ref "R9") (pin "2_SENSE") (pinfunction "2K_2_SENSE") (pintype "passive"))
      (node (ref "U9") (pin "22") (pinfunction "PB10_22") (pintype "bidirectional"))
    )
    (net (code "108") (name "SILENT") (class "Default")
      (node (ref "U12") (pin "8") (pinfunction "S_8") (pintype "bidirectional"))
    )
    (net (code "109") (name "SWCLK") (class "Default")
      (node (ref "J9") (pin "4") (pinfunction "4_4") (pintype "bidirectional"))
      (node (ref "U9") (pin "38") (pinfunction "PA14_38") (pintype "bidirectional"))
    )
    (net (code "110") (name "SWDIO") (class "Default")
      (node (ref "J9") (pin "2") (pinfunction "2_2") (pintype "bidirectional"))
      (node (ref "U9") (pin "37") (pinfunction "PA13_37") (pintype "bidirectional"))
    )
    (net (code "111") (name "SWO") (class "Default")
      (node (ref "J9") (pin "6") (pinfunction "6_6") (pintype "bidirectional"))
      (node (ref "U9") (pin "40") (pinfunction "PB3_40") (pintype "bidirectional"))
    )
    (net (code "112") (name "TEMP_SENSE") (class "Default")
      (node (ref "U10") (pin "3") (pinfunction "VOUT_3") (pintype "bidirectional"))
      (node (ref "U9") (pin "25") (pinfunction "PB11_25") (pintype "bidirectional"))
    )
    (net (code "113") (name "VIN") (class "Default")
      (node (ref "C1") (pin "+") (pinfunction "+_+") (pintype "passive"))
      (node (ref "C10") (pin "1") (pinfunction "1_1") (pintype "passive"))
      (node (ref "C11") (pin "1") (pinfunction "1_1") (pintype "passive"))
      (node (ref "C12") (pin "1") (pinfunction "1_1") (pintype "passive"))
      (node (ref "C13") (pin "1") (pinfunction "1_1") (pintype "passive"))
      (node (ref "C14") (pin "1") (pinfunction "1_1") (pintype "passive"))
      (node (ref "C15") (pin "1") (pinfunction "1_1") (pintype "passive"))
      (node (ref "C16") (pin "1") (pinfunction "1_1") (pintype "passive"))
      (node (ref "C17") (pin "1") (pinfunction "1_1") (pintype "passive"))
      (node (ref "C18") (pin "1") (pinfunction "1_1") (pintype "passive"))
      (node (ref "C19") (pin "1") (pinfunction "1_1") (pintype "passive"))
      (node (ref "C2") (pin "+") (pinfunction "+_+") (pintype "passive"))
      (node (ref "C20") (pin "1") (pinfunction "1_1") (pintype "passive"))
      (node (ref "C21") (pin "1") (pinfunction "1_1") (pintype "passive"))
      (node (ref "C22") (pin "1") (pinfunction "1_1") (pintype "passive"))
      (node (ref "C23") (pin "1") (pinfunction "1_1") (pintype "passive"))
      (node (ref "C24") (pin "1") (pinfunction "1_1") (pintype "passive"))
      (node (ref "C3") (pin "+") (pinfunction "+_+") (pintype "passive"))
      (node (ref "C31") (pin "1") (pinfunction "1_1") (pintype "passive"))
      (node (ref "C4") (pin "1") (pinfunction "1_1") (pintype "passive"))
      (node (ref "C5") (pin "1") (pinfunction "1_1") (pintype "passive"))
      (node (ref "C6") (pin "1") (pinfunction "1_1") (pintype "passive"))
      (node (ref "C7") (pin "1") (pinfunction "1_1") (pintype "passive"))
      (node (ref "C8") (pin "1") (pinfunction "1_1") (pintype "passive"))
      (node (ref "C9") (pin "1") (pinfunction "1_1") (pintype "passive"))
      (node (ref "D1") (pin "A") (pinfunction "A_A") (pintype "passive"))
      (node (ref "J1") (pin "1") (pinfunction "1_1") (pintype "bidirectional"))
      (node (ref "L1") (pin "1") (pinfunction "1_1") (pintype "passive"))
      (node (ref "Q1") (pin "11") (pinfunction "D_11") (pintype "passive"))
      (node (ref "Q1") (pin "12") (pinfunction "D_12") (pintype "passive"))
      (node (ref "Q1") (pin "15") (pinfunction "D_15") (pintype "passive"))
      (node (ref "Q1") (pin "16") (pinfunction "D_16") (pintype "passive"))
      (node (ref "Q1") (pin "19") (pinfunction "D_19") (pintype "passive"))
      (node (ref "Q1") (pin "20") (pinfunction "D_20") (pintype "passive"))
      (node (ref "Q1") (pin "23") (pinfunction "D_23") (pintype "passive"))
      (node (ref "Q1") (pin "24") (pinfunction "D_24") (pintype "passive"))
      (node (ref "Q1") (pin "27") (pinfunction "D_27") (pintype "passive"))
      (node (ref "Q1") (pin "28") (pinfunction "D_28") (pintype "passive"))
      (node (ref "Q1") (pin "3") (pinfunction "D_3") (pintype "passive"))
      (node (ref "Q1") (pin "4") (pinfunction "D_4") (pintype "passive"))
      (node (ref "Q1") (pin "7") (pinfunction "D_7") (pintype "passive"))
      (node (ref "Q1") (pin "8") (pinfunction "D_8") (pintype "passive"))
      (node (ref "Q3") (pin "11") (pinfunction "D_11") (pintype "passive"))
      (node (ref "Q3") (pin "12") (pinfunction "D_12") (pintype "passive"))
      (node (ref "Q3") (pin "15") (pinfunction "D_15") (pintype "passive"))
      (node (ref "Q3") (pin "16") (pinfunction "D_16") (pintype "passive"))
      (node (ref "Q3") (pin "19") (pinfunction "D_19") (pintype "passive"))
      (node (ref "Q3") (pin "20") (pinfunction "D_20") (pintype "passive"))
      (node (ref "Q3") (pin "23") (pinfunction "D_23") (pintype "passive"))
      (node (ref "Q3") (pin "24") (pinfunction "D_24") (pintype "passive"))
      (node (ref "Q3") (pin "27") (pinfunction "D_27") (pintype "passive"))
      (node (ref "Q3") (pin "28") (pinfunction "D_28") (pintype "passive"))
      (node (ref "Q3") (pin "3") (pinfunction "D_3") (pintype "passive"))
      (node (ref "Q3") (pin "4") (pinfunction "D_4") (pintype "passive"))
      (node (ref "Q3") (pin "7") (pinfunction "D_7") (pintype "passive"))
      (node (ref "Q3") (pin "8") (pinfunction "D_8") (pintype "passive"))
      (node (ref "Q5") (pin "11") (pinfunction "D_11") (pintype "passive"))
      (node (ref "Q5") (pin "12") (pinfunction "D_12") (pintype "passive"))
      (node (ref "Q5") (pin "15") (pinfunction "D_15") (pintype "passive"))
      (node (ref "Q5") (pin "16") (pinfunction "D_16") (pintype "passive"))
      (node (ref "Q5") (pin "19") (pinfunction "D_19") (pintype "passive"))
      (node (ref "Q5") (pin "20") (pinfunction "D_20") (pintype "passive"))
      (node (ref "Q5") (pin "23") (pinfunction "D_23") (pintype "passive"))
      (node (ref "Q5") (pin "24") (pinfunction "D_24") (pintype "passive"))
      (node (ref "Q5") (pin "27") (pinfunction "D_27") (pintype "passive"))
      (node (ref "Q5") (pin "28") (pinfunction "D_28") (pintype "passive"))
      (node (ref "Q5") (pin "3") (pinfunction "D_3") (pintype "passive"))
      (node (ref "Q5") (pin "4") (pinfunction "D_4") (pintype "passive"))
      (node (ref "Q5") (pin "7") (pinfunction "D_7") (pintype "passive"))
      (node (ref "Q5") (pin "8") (pinfunction "D_8") (pintype "passive"))
      (node (ref "R25") (pin "2") (pinfunction "2_2") (pintype "bidirectional"))
    )
    (net (code "114") (name "unconnected-(AIM1-PadAIM)") (class "Default")
      (node (ref "AIM1") (pin "AIM") (pinfunction "AIM_AIM") (pintype "passive"))
    )
    (net (code "115") (name "unconnected-(AIM2-PadAIM)") (class "Default")
      (node (ref "AIM2") (pin "AIM") (pinfunction "AIM_AIM") (pintype "passive"))
    )
    (net (code "116") (name "unconnected-(AIM3-PadAIM)") (class "Default")
      (node (ref "AIM3") (pin "AIM") (pinfunction "AIM_AIM") (pintype "passive"))
    )
    (net (code "117") (name "unconnected-(U4-PGOOD-Pad8)") (class "Default")
      (node (ref "U4") (pin "8") (pinfunction "PGOOD_8") (pintype "bidirectional"))
    )
    (net (code "118") (name "unconnected-(U4-RT-Pad7)") (class "Default")
      (node (ref "U4") (pin "7") (pinfunction "RT_7") (pintype "bidirectional"))
    )
    (net (code "119") (name "unconnected-(U10-NC1-Pad1)") (class "Default")
      (node (ref "U10") (pin "1") (pinfunction "NC1_1") (pintype "bidirectional"))
    )
    (net (code "120") (name "unconnected-(U10-NC2-Pad5)") (class "Default")
      (node (ref "U10") (pin "5") (pinfunction "NC2_5") (pintype "bidirectional"))
    )
    (net (code "121") (name "~{INVALID}") (class "Default")
      (node (ref "U11") (pin "10") (pinfunction "~{INVALID}_10") (pintype "bidirectional"))
    )
    (net (code "122") (name "~{LDO_CN}") (class "Default")
      (node (ref "R19") (pin "1") (pinfunction "1_1") (pintype "bidirectional"))
      (node (ref "U8") (pin "5") (pinfunction "ST_5") (pintype "bidirectional"))
    )
    (net (code "123") (name "~{NRST}") (class "Default")
      (node (ref "J9") (pin "8") (pinfunction "8_8") (pintype "bidirectional"))
      (node (ref "U9") (pin "7") (pinfunction "PG10-NRST_7") (pintype "bidirectional"))
    )
    (net (code "124") (name "~{STLINK_CN}") (class "Default")
      (node (ref "R16") (pin "1") (pinfunction "1_1") (pintype "bidirectional"))
      (node (ref "U7") (pin "5") (pinfunction "ST_5") (pintype "bidirectional"))
    )
  )
)
